# greenhouseSchematic.net
KiCad netlist of a schematic drawn in Altium Designer
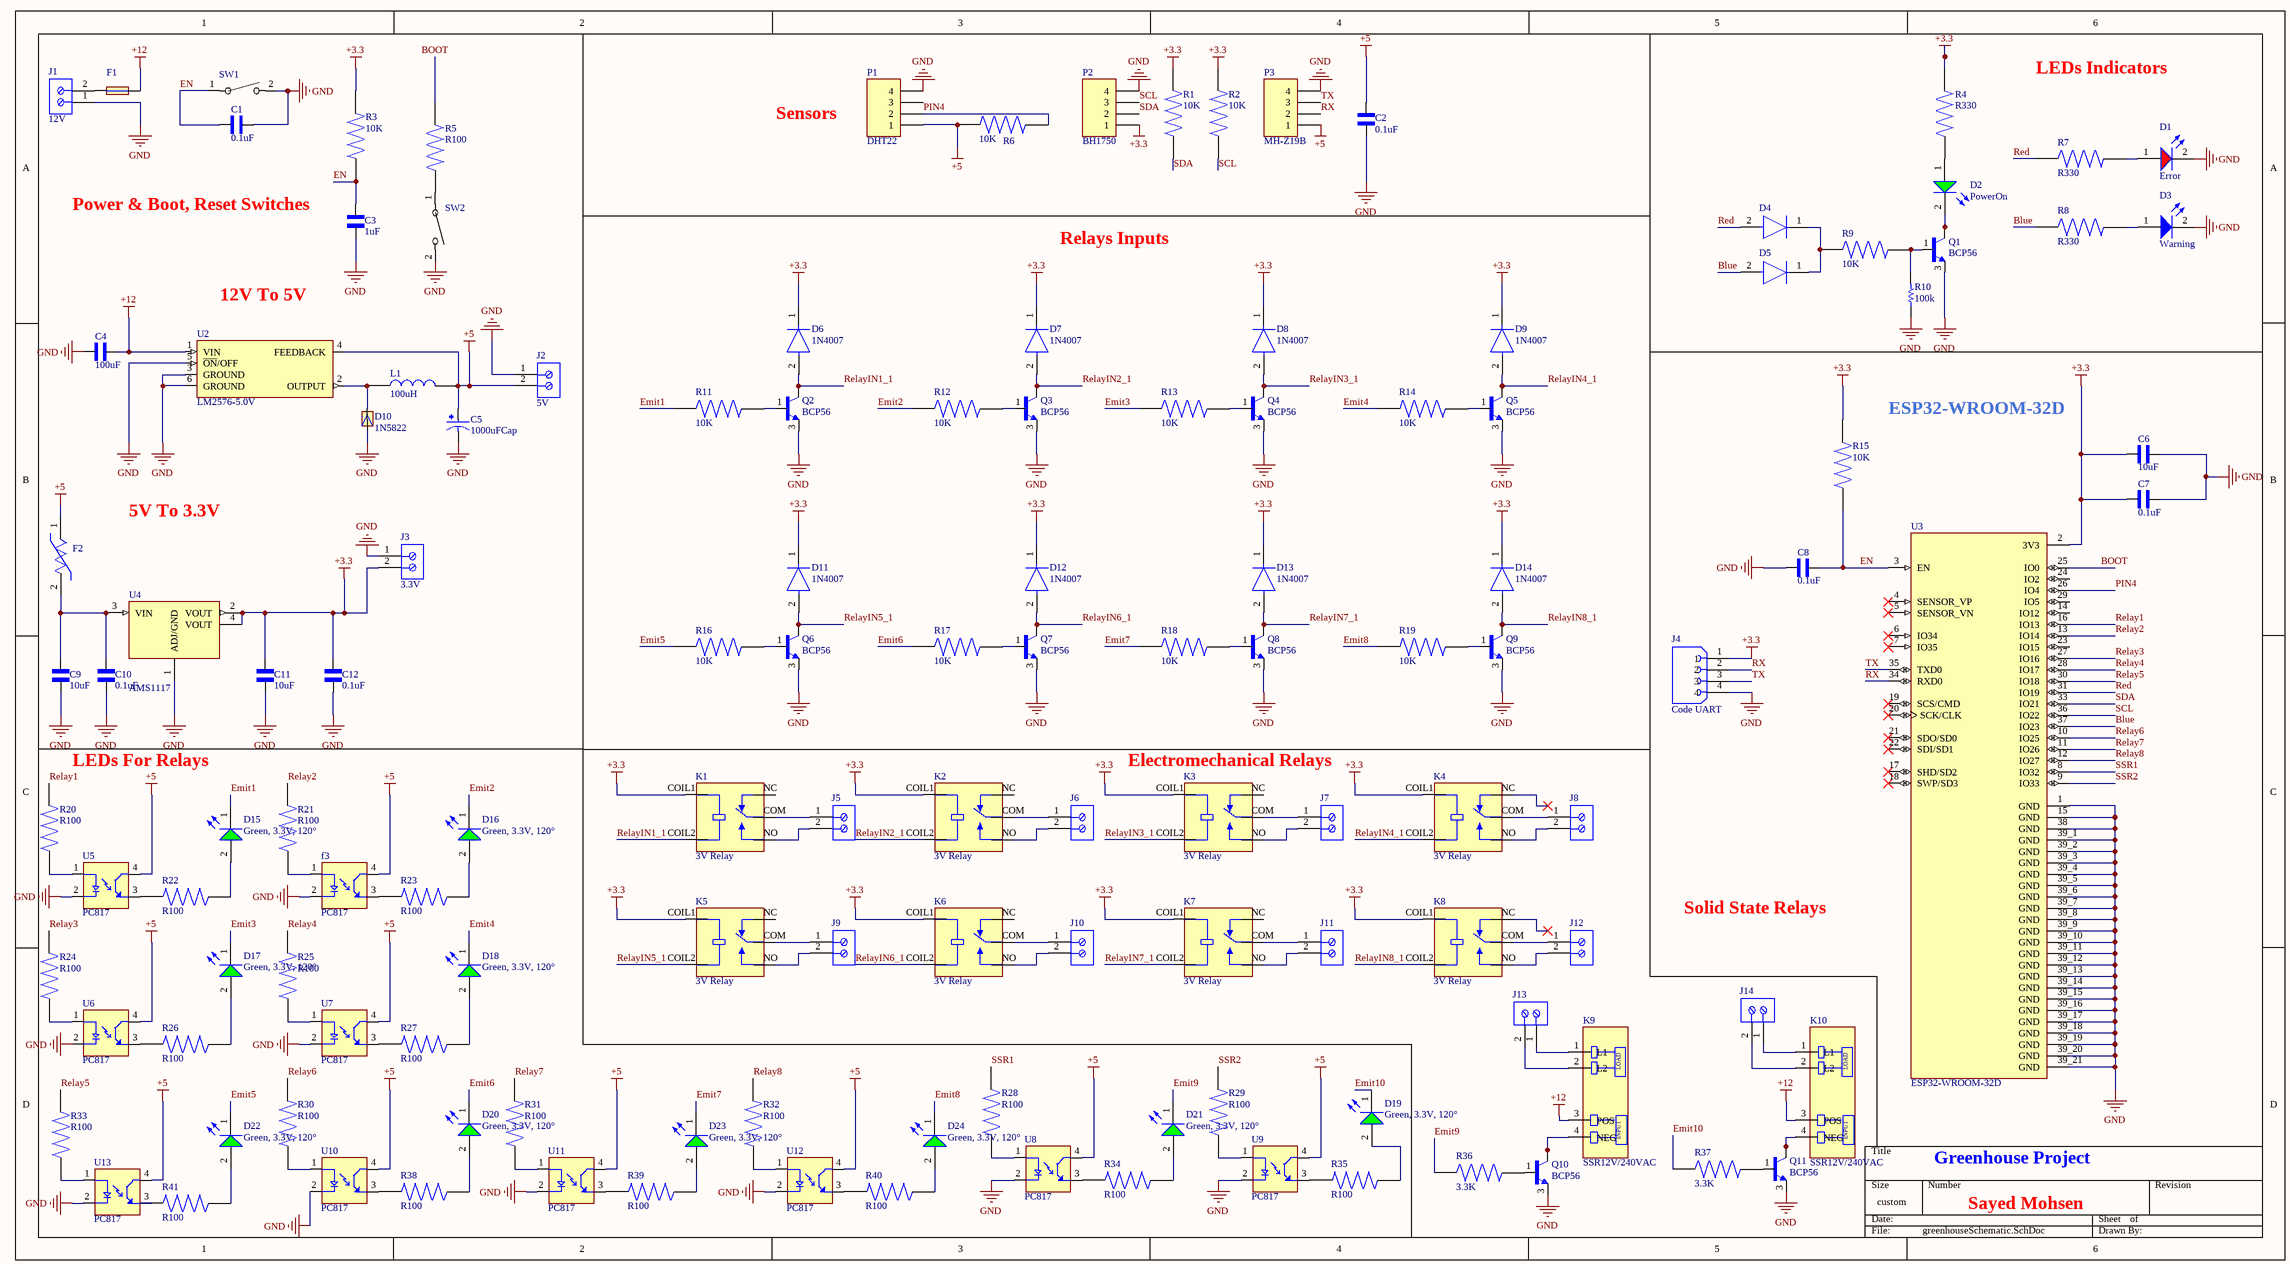
[diagram p0: greenhouseSchematic.SchDoc]

(export (version "E")
  (design (tool "Eeschema 10.0.6"))
  (components
    (comp (ref "C1")
      (value "0.1uF")
      (footprint "Capacitor0.1uF")
      (description "SMD Capacitor X7S(EIA) with Capacitance: 0.10uF Tol. 10%. Rated Voltage: 16Vdc")
      (fields (field (name "MF") "Murata") (field (name "MP") "GRM033C71C104KE14D"))
      (libsource (lib "greenhouse_SchLib") (part "Capacitor0.1uF"))
    )
    (comp (ref "C2")
      (value "0.1uF")
      (footprint "Capacitor0.1uF")
      (description "SMD Capacitor X7S(EIA) with Capacitance: 0.10uF Tol. 10%. Rated Voltage: 16Vdc")
      (fields (field (name "MF") "Murata") (field (name "MP") "GRM033C71C104KE14D"))
      (libsource (lib "") (part "Capacitor0.1uF_1"))
    )
    (comp (ref "C3")
      (value "1uF")
      (footprint "CAPACITOR1UF")
      (description "SMD capacitor X5R(EIA) with capacitance 1.0uF Tol.20%. Rated voltage 10Vdc 85C")
      (fields (field (name "MF") "Murata") (field (name "MP") "GRM033R61A105ME44J"))
      (libsource (lib "greenhouse_SchLib") (part "Capacitor1uF"))
    )
    (comp (ref "C4")
      (value "100uF")
      (footprint "Capacitor10uF")
      (description "SMD Capacitor X5R(EIA) with Capacitance: 10uF Tol. 10%. Rated Voltage: 10Vdc")
      (fields (field (name "MF") "Murata") (field (name "MP") "GRM21BR61A106KE19K"))
      (libsource (lib "greenhouse_SchLib") (part "Capacitor10uF"))
    )
    (comp (ref "C5")
      (value "1000uFCap")
      (footprint "1000uFCap")
      (description "CAP ALUM 1000UF 20% 10V SMD")
      (fields (field (name "MP") "EEE-FN1A102P") (field (name "MF") "Panasonic Electronic Components"))
      (libsource (lib "greenhouse_SchLib") (part "1000uFCap"))
    )
    (comp (ref "C6")
      (value "10uF")
      (footprint "Capacitor10uF")
      (description "SMD Capacitor X5R(EIA) with Capacitance: 10uF Tol. 10%. Rated Voltage: 10Vdc")
      (fields (field (name "MF") "Murata") (field (name "MP") "GRM21BR61A106KE19K"))
      (libsource (lib "") (part "Capacitor10uF_1"))
    )
    (comp (ref "C7")
      (value "0.1uF")
      (footprint "Capacitor0.1uF")
      (description "SMD Capacitor X7S(EIA) with Capacitance: 0.10uF Tol. 10%. Rated Voltage: 16Vdc")
      (fields (field (name "MF") "Murata") (field (name "MP") "GRM033C71C104KE14D"))
      (libsource (lib "greenhouse_SchLib") (part "Capacitor0.1uF"))
    )
    (comp (ref "C8")
      (value "0.1uF")
      (footprint "Capacitor0.1uF")
      (description "SMD Capacitor X7S(EIA) with Capacitance: 0.10uF Tol. 10%. Rated Voltage: 16Vdc")
      (fields (field (name "MF") "Murata") (field (name "MP") "GRM033C71C104KE14D"))
      (libsource (lib "greenhouse_SchLib") (part "Capacitor0.1uF"))
    )
    (comp (ref "C9")
      (value "10uF")
      (footprint "Capacitor10uF")
      (description "SMD Capacitor X5R(EIA) with Capacitance: 10uF Tol. 10%. Rated Voltage: 10Vdc")
      (fields (field (name "MF") "Murata") (field (name "MP") "GRM21BR61A106KE19K"))
      (libsource (lib "") (part "Capacitor10uF_2"))
    )
    (comp (ref "C10")
      (value "0.1uF")
      (footprint "Capacitor0.1uF")
      (description "SMD Capacitor X7S(EIA) with Capacitance: 0.10uF Tol. 10%. Rated Voltage: 16Vdc")
      (fields (field (name "MF") "Murata") (field (name "MP") "GRM033C71C104KE14D"))
      (libsource (lib "") (part "Capacitor0.1uF_1"))
    )
    (comp (ref "C11")
      (value "10uF")
      (footprint "Capacitor10uF")
      (description "SMD Capacitor X5R(EIA) with Capacitance: 10uF Tol. 10%. Rated Voltage: 10Vdc")
      (fields (field (name "MF") "Murata") (field (name "MP") "GRM21BR61A106KE19K"))
      (libsource (lib "") (part "Capacitor10uF_2"))
    )
    (comp (ref "C12")
      (value "0.1uF")
      (footprint "Capacitor0.1uF")
      (description "SMD Capacitor X7S(EIA) with Capacitance: 0.10uF Tol. 10%. Rated Voltage: 16Vdc")
      (fields (field (name "MF") "Murata") (field (name "MP") "GRM033C71C104KE14D"))
      (libsource (lib "") (part "Capacitor0.1uF_1"))
    )
    (comp (ref "D1")
      (value "Error")
      (footprint "redLed")
      (libsource (lib "greenhouse_SchLib") (part "redLed"))
    )
    (comp (ref "D2")
      (value "PowerOn")
      (footprint "greenLed")
      (libsource (lib "greenhouse_SchLib") (part "greenLed"))
    )
    (comp (ref "D3")
      (value "Warning")
      (footprint "blueLed")
      (libsource (lib "greenhouse_SchLib") (part "blueLed"))
    )
    (comp (ref "D4")
      (value "1N4007")
      (footprint "1N4007")
      (description "Rectifier diode 1000 V 1 A DO-41, ,")
      (fields
        (field (name "MANUFACTURER") "Diotec")
        (field (name "OCTOPART") "https://octopart.com/1n4007-diotec-4040411")
      )
      (libsource (lib "greenhouse_SchLib") (part "1N4007"))
    )
    (comp (ref "D5")
      (value "1N4007")
      (footprint "1N4007")
      (description "Rectifier diode 1000 V 1 A DO-41, ,")
      (fields
        (field (name "MANUFACTURER") "Diotec")
        (field (name "OCTOPART") "https://octopart.com/1n4007-diotec-4040411")
      )
      (libsource (lib "greenhouse_SchLib") (part "1N4007"))
    )
    (comp (ref "D6")
      (value "1N4007")
      (footprint "1N4007")
      (description "Rectifier diode 1000 V 1 A DO-41, ,")
      (fields
        (field (name "MANUFACTURER") "Diotec")
        (field (name "OCTOPART") "https://octopart.com/1n4007-diotec-4040411")
      )
      (libsource (lib "greenhouse_SchLib") (part "1N4007"))
    )
    (comp (ref "D7")
      (value "1N4007")
      (footprint "1N4007")
      (description "Rectifier diode 1000 V 1 A DO-41, ,")
      (fields
        (field (name "MANUFACTURER") "Diotec")
        (field (name "OCTOPART") "https://octopart.com/1n4007-diotec-4040411")
      )
      (libsource (lib "greenhouse_SchLib") (part "1N4007"))
    )
    (comp (ref "D8")
      (value "1N4007")
      (footprint "1N4007")
      (description "Rectifier diode 1000 V 1 A DO-41, ,")
      (fields
        (field (name "MANUFACTURER") "Diotec")
        (field (name "OCTOPART") "https://octopart.com/1n4007-diotec-4040411")
      )
      (libsource (lib "greenhouse_SchLib") (part "1N4007"))
    )
    (comp (ref "D9")
      (value "1N4007")
      (footprint "1N4007")
      (description "Rectifier diode 1000 V 1 A DO-41, ,")
      (fields
        (field (name "MANUFACTURER") "Diotec")
        (field (name "OCTOPART") "https://octopart.com/1n4007-diotec-4040411")
      )
      (libsource (lib "greenhouse_SchLib") (part "1N4007"))
    )
    (comp (ref "D10")
      (value "1N5822")
      (footprint "1N5822Diode")
      (description "Schottky, DO-201, 40V, 3A, 150Â°C")
      (fields (field (name "MF") "Diotec Semiconductor"))
      (libsource (lib "greenhouse_SchLib") (part "1N5822 Diode"))
    )
    (comp (ref "D11")
      (value "1N4007")
      (footprint "1N4007")
      (description "Rectifier diode 1000 V 1 A DO-41, ,")
      (fields
        (field (name "MANUFACTURER") "Diotec")
        (field (name "OCTOPART") "https://octopart.com/1n4007-diotec-4040411")
      )
      (libsource (lib "greenhouse_SchLib") (part "1N4007"))
    )
    (comp (ref "D12")
      (value "1N4007")
      (footprint "1N4007")
      (description "Rectifier diode 1000 V 1 A DO-41, ,")
      (fields
        (field (name "MANUFACTURER") "Diotec")
        (field (name "OCTOPART") "https://octopart.com/1n4007-diotec-4040411")
      )
      (libsource (lib "greenhouse_SchLib") (part "1N4007"))
    )
    (comp (ref "D13")
      (value "1N4007")
      (footprint "1N4007")
      (description "Rectifier diode 1000 V 1 A DO-41, ,")
      (fields
        (field (name "MANUFACTURER") "Diotec")
        (field (name "OCTOPART") "https://octopart.com/1n4007-diotec-4040411")
      )
      (libsource (lib "greenhouse_SchLib") (part "1N4007"))
    )
    (comp (ref "D14")
      (value "1N4007")
      (footprint "1N4007")
      (description "Rectifier diode 1000 V 1 A DO-41, ,")
      (fields
        (field (name "MANUFACTURER") "Diotec")
        (field (name "OCTOPART") "https://octopart.com/1n4007-diotec-4040411")
      )
      (libsource (lib "greenhouse_SchLib") (part "1N4007"))
    )
    (comp (ref "D15")
      (value "Green, 3.3V, 120°")
      (footprint "newgreenled")
      (description "WL-SMCC Mono-color Chip LED Compact, SMT, size 0402, Green, 3.3V, 120°")
      (fields
        (field (name "MANUFACTURER PART NUMBER") "150040GS73220")
        (field (name "MANUFACTURER") "Wurth Elektronik")
      )
      (libsource (lib "greenhouse_SchLib") (part "GreenLed_1"))
    )
    (comp (ref "D16")
      (value "Green, 3.3V, 120°")
      (footprint "newgreenled")
      (description "WL-SMCC Mono-color Chip LED Compact, SMT, size 0402, Green, 3.3V, 120°")
      (fields
        (field (name "MANUFACTURER PART NUMBER") "150040GS73220")
        (field (name "MANUFACTURER") "Wurth Elektronik")
      )
      (libsource (lib "greenhouse_SchLib") (part "GreenLed_1"))
    )
    (comp (ref "D17")
      (value "Green, 3.3V, 120°")
      (footprint "newgreenled")
      (description "WL-SMCC Mono-color Chip LED Compact, SMT, size 0402, Green, 3.3V, 120°")
      (fields
        (field (name "MANUFACTURER PART NUMBER") "150040GS73220")
        (field (name "MANUFACTURER") "Wurth Elektronik")
      )
      (libsource (lib "greenhouse_SchLib") (part "GreenLed_1"))
    )
    (comp (ref "D18")
      (value "Green, 3.3V, 120°")
      (footprint "newgreenled")
      (description "WL-SMCC Mono-color Chip LED Compact, SMT, size 0402, Green, 3.3V, 120°")
      (fields
        (field (name "MANUFACTURER PART NUMBER") "150040GS73220")
        (field (name "MANUFACTURER") "Wurth Elektronik")
      )
      (libsource (lib "greenhouse_SchLib") (part "GreenLed_1"))
    )
    (comp (ref "D19")
      (value "Green, 3.3V, 120°")
      (footprint "newgreenled")
      (description "WL-SMCC Mono-color Chip LED Compact, SMT, size 0402, Green, 3.3V, 120°")
      (fields
        (field (name "MANUFACTURER PART NUMBER") "150040GS73220")
        (field (name "MANUFACTURER") "Wurth Elektronik")
      )
      (libsource (lib "greenhouse_SchLib") (part "GreenLed_1"))
    )
    (comp (ref "D20")
      (value "Green, 3.3V, 120°")
      (footprint "newgreenled")
      (description "WL-SMCC Mono-color Chip LED Compact, SMT, size 0402, Green, 3.3V, 120°")
      (fields
        (field (name "MANUFACTURER PART NUMBER") "150040GS73220")
        (field (name "MANUFACTURER") "Wurth Elektronik")
      )
      (libsource (lib "greenhouse_SchLib") (part "GreenLed_1"))
    )
    (comp (ref "D21")
      (value "Green, 3.3V, 120°")
      (footprint "newgreenled")
      (description "WL-SMCC Mono-color Chip LED Compact, SMT, size 0402, Green, 3.3V, 120°")
      (fields
        (field (name "MANUFACTURER PART NUMBER") "150040GS73220")
        (field (name "MANUFACTURER") "Wurth Elektronik")
      )
      (libsource (lib "greenhouse_SchLib") (part "GreenLed_1"))
    )
    (comp (ref "D22")
      (value "Green, 3.3V, 120°")
      (footprint "newgreenled")
      (description "WL-SMCC Mono-color Chip LED Compact, SMT, size 0402, Green, 3.3V, 120°")
      (fields
        (field (name "MANUFACTURER PART NUMBER") "150040GS73220")
        (field (name "MANUFACTURER") "Wurth Elektronik")
      )
      (libsource (lib "greenhouse_SchLib") (part "GreenLed_1"))
    )
    (comp (ref "D23")
      (value "Green, 3.3V, 120°")
      (footprint "newgreenled")
      (description "WL-SMCC Mono-color Chip LED Compact, SMT, size 0402, Green, 3.3V, 120°")
      (fields
        (field (name "MANUFACTURER PART NUMBER") "150040GS73220")
        (field (name "MANUFACTURER") "Wurth Elektronik")
      )
      (libsource (lib "greenhouse_SchLib") (part "GreenLed_1"))
    )
    (comp (ref "D24")
      (value "Green, 3.3V, 120°")
      (footprint "newgreenled")
      (description "WL-SMCC Mono-color Chip LED Compact, SMT, size 0402, Green, 3.3V, 120°")
      (fields
        (field (name "MANUFACTURER PART NUMBER") "150040GS73220")
        (field (name "MANUFACTURER") "Wurth Elektronik")
      )
      (libsource (lib "greenhouse_SchLib") (part "GreenLed_1"))
    )
    (comp (ref "F1")
      (value "1812L200/12DR")
      (footprint "FUSE_1812L200/12DR")
      (description "Polymeric PTC Resettable Fuse 12V 2A Ih Surface Mount 1812 (4532 Metric), Concave")
      (fields (field (name "MF") "Littelfuse Inc."))
      (libsource (lib "greenhouse_SchLib") (part "1812L200/12DR"))
    )
    (comp (ref "F2")
      (value "0ZCK0075FF2E")
      (footprint "ptc6v")
      (description "PTC RESET FUSE 6V 750MA 0805")
      (libsource (lib "greenhouse_SchLib") (part "ptc6v"))
    )
    (comp (ref "f3")
      (value "PC817")
      (footprint "PC817")
      (description "Optocoupler DC-IN 1-CH Transistor DC-OUT 4-Pin DIP SMD T/R")
      (fields (field (name "MF") "Sharp Microelectronics") (field (name "MP") "PC817X2NIP1B"))
      (libsource (lib "greenhouse_SchLib") (part "PC817"))
    )
    (comp (ref "J1") (value "12V") (footprint "screw") (libsource (lib "") (part "screw_1")))
    (comp (ref "J2") (value "5V") (footprint "screw") (libsource (lib "") (part "screw_1")))
    (comp (ref "J3") (value "3.3V") (footprint "screw") (libsource (lib "") (part "screw_1")))
    (comp (ref "J4")
      (value "Code UART")
      (footprint "Fpinheader")
      (description "4 Position Header Connector 0.100 (2.54mm) Through Hole Tin")
      (fields (field (name "MF") "Sullins Connector") (field (name "MP") "PPTC041LFBN-RC"))
      (libsource (lib "greenhouse_SchLib") (part "FPinheader"))
    )
    (comp (ref "J5") (value "~") (footprint "screw") (libsource (lib "") (part "screw_1")))
    (comp (ref "J6") (value "~") (footprint "screw") (libsource (lib "") (part "screw_1")))
    (comp (ref "J7") (value "~") (footprint "screw") (libsource (lib "") (part "screw_1")))
    (comp (ref "J8") (value "~") (footprint "screw") (libsource (lib "") (part "screw_1")))
    (comp (ref "J9") (value "~") (footprint "screw") (libsource (lib "") (part "screw_1")))
    (comp (ref "J10") (value "~") (footprint "screw") (libsource (lib "") (part "screw_1")))
    (comp (ref "J11") (value "~") (footprint "screw") (libsource (lib "") (part "screw_1")))
    (comp (ref "J12") (value "~") (footprint "screw") (libsource (lib "") (part "screw_1")))
    (comp (ref "J13") (value "~") (footprint "screw") (libsource (lib "greenhouse_SchLib") (part "screw")))
    (comp (ref "J14") (value "~") (footprint "screw") (libsource (lib "greenhouse_SchLib") (part "screw")))
    (comp (ref "K1")
      (value "3V Relay")
      (footprint "3V Relay")
      (description "Relays General Purpose Non Latching 3VDC SPDT 10A (250VAC) Max 5PIN")
      (fields (field (name "MF") "Songle Relay") (field (name "MP") "SRD-03VDC-SL-C"))
      (libsource (lib "greenhouse_SchLib") (part "3V Relay"))
    )
    (comp (ref "K2")
      (value "3V Relay")
      (footprint "3V Relay")
      (description "Relays General Purpose Non Latching 3VDC SPDT 10A (250VAC) Max 5PIN")
      (fields (field (name "MF") "Songle Relay") (field (name "MP") "SRD-03VDC-SL-C"))
      (libsource (lib "greenhouse_SchLib") (part "3V Relay"))
    )
    (comp (ref "K3")
      (value "3V Relay")
      (footprint "3V Relay")
      (description "Relays General Purpose Non Latching 3VDC SPDT 10A (250VAC) Max 5PIN")
      (fields (field (name "MF") "Songle Relay") (field (name "MP") "SRD-03VDC-SL-C"))
      (libsource (lib "greenhouse_SchLib") (part "3V Relay"))
    )
    (comp (ref "K4")
      (value "3V Relay")
      (footprint "3V Relay")
      (description "Relays General Purpose Non Latching 3VDC SPDT 10A (250VAC) Max 5PIN")
      (fields (field (name "MF") "Songle Relay") (field (name "MP") "SRD-03VDC-SL-C"))
      (libsource (lib "greenhouse_SchLib") (part "3V Relay"))
    )
    (comp (ref "K5")
      (value "3V Relay")
      (footprint "3V Relay")
      (description "Relays General Purpose Non Latching 3VDC SPDT 10A (250VAC) Max 5PIN")
      (fields (field (name "MF") "Songle Relay") (field (name "MP") "SRD-03VDC-SL-C"))
      (libsource (lib "greenhouse_SchLib") (part "3V Relay"))
    )
    (comp (ref "K6")
      (value "3V Relay")
      (footprint "3V Relay")
      (description "Relays General Purpose Non Latching 3VDC SPDT 10A (250VAC) Max 5PIN")
      (fields (field (name "MF") "Songle Relay") (field (name "MP") "SRD-03VDC-SL-C"))
      (libsource (lib "greenhouse_SchLib") (part "3V Relay"))
    )
    (comp (ref "K7")
      (value "3V Relay")
      (footprint "3V Relay")
      (description "Relays General Purpose Non Latching 3VDC SPDT 10A (250VAC) Max 5PIN")
      (fields (field (name "MF") "Songle Relay") (field (name "MP") "SRD-03VDC-SL-C"))
      (libsource (lib "greenhouse_SchLib") (part "3V Relay"))
    )
    (comp (ref "K8")
      (value "3V Relay")
      (footprint "3V Relay")
      (description "Relays General Purpose Non Latching 3VDC SPDT 10A (250VAC) Max 5PIN")
      (fields (field (name "MF") "Songle Relay") (field (name "MP") "SRD-03VDC-SL-C"))
      (libsource (lib "greenhouse_SchLib") (part "3V Relay"))
    )
    (comp (ref "K9")
      (value "SSR12V/240VAC")
      (footprint "SSR12V/240VAC")
      (description "Solid State SPST-NO (1 Form A) 4-SIP")
      (fields (field (name "MF") "Omron Automation") (field (name "MP") "G3MB-202P DC12"))
      (libsource (lib "greenhouse_SchLib") (part "SSR12V/240VAC"))
    )
    (comp (ref "K10")
      (value "SSR12V/240VAC")
      (footprint "SSR12V/240VAC")
      (description "Solid State SPST-NO (1 Form A) 4-SIP")
      (fields (field (name "MF") "Omron Automation") (field (name "MP") "G3MB-202P DC12"))
      (libsource (lib "greenhouse_SchLib") (part "SSR12V/240VAC"))
    )
    (comp (ref "L1")
      (value "100uH")
      (footprint "100uH Inductor")
      (description "Inductor with Inductance 100uH Tol.+/-20% Package 1212 (3030)")
      (fields (field (name "MF") "Murata") (field (name "MP") "LQH3NPH101MMEL"))
      (libsource (lib "greenhouse_SchLib") (part "100uH Inductor"))
    )
    (comp (ref "P1")
      (value "DHT22")
      (footprint "HDR1X4")
      (description "Header, 4-Pin")
      (fields (field (name "PUBLISHER") "Altium Limited"))
      (libsource (lib "Miscellaneous Connectors") (part "Header 4"))
    )
    (comp (ref "P2")
      (value "BH1750")
      (footprint "HDR1X4")
      (description "Header, 4-Pin")
      (fields (field (name "PUBLISHER") "Altium Limited"))
      (libsource (lib "Miscellaneous Connectors") (part "Header 4"))
    )
    (comp (ref "P3")
      (value "MH-Z19B")
      (footprint "HDR1X4")
      (description "Header, 4-Pin")
      (fields (field (name "PUBLISHER") "Altium Limited"))
      (libsource (lib "Miscellaneous Connectors") (part "Header 4"))
    )
    (comp (ref "Q1")
      (value "BCP56")
      (footprint "BCP56")
      (description "Bipolar (BJT) Transistor NPN 80 V 1 A 130MHz 1.5 W Surface Mount SOT-223 (TO-261)")
      (fields (field (name "MF") "ON Semiconductor"))
      (libsource (lib "greenhouse_SchLib") (part "BCP56"))
    )
    (comp (ref "Q2")
      (value "BCP56")
      (footprint "BCP56")
      (description "Bipolar (BJT) Transistor NPN 80 V 1 A 130MHz 1.5 W Surface Mount SOT-223 (TO-261)")
      (fields (field (name "MF") "ON Semiconductor"))
      (libsource (lib "greenhouse_SchLib") (part "BCP56"))
    )
    (comp (ref "Q3")
      (value "BCP56")
      (footprint "BCP56")
      (description "Bipolar (BJT) Transistor NPN 80 V 1 A 130MHz 1.5 W Surface Mount SOT-223 (TO-261)")
      (fields (field (name "MF") "ON Semiconductor"))
      (libsource (lib "greenhouse_SchLib") (part "BCP56"))
    )
    (comp (ref "Q4")
      (value "BCP56")
      (footprint "BCP56")
      (description "Bipolar (BJT) Transistor NPN 80 V 1 A 130MHz 1.5 W Surface Mount SOT-223 (TO-261)")
      (fields (field (name "MF") "ON Semiconductor"))
      (libsource (lib "greenhouse_SchLib") (part "BCP56"))
    )
    (comp (ref "Q5")
      (value "BCP56")
      (footprint "BCP56")
      (description "Bipolar (BJT) Transistor NPN 80 V 1 A 130MHz 1.5 W Surface Mount SOT-223 (TO-261)")
      (fields (field (name "MF") "ON Semiconductor"))
      (libsource (lib "greenhouse_SchLib") (part "BCP56"))
    )
    (comp (ref "Q6")
      (value "BCP56")
      (footprint "BCP56")
      (description "Bipolar (BJT) Transistor NPN 80 V 1 A 130MHz 1.5 W Surface Mount SOT-223 (TO-261)")
      (fields (field (name "MF") "ON Semiconductor"))
      (libsource (lib "greenhouse_SchLib") (part "BCP56"))
    )
    (comp (ref "Q7")
      (value "BCP56")
      (footprint "BCP56")
      (description "Bipolar (BJT) Transistor NPN 80 V 1 A 130MHz 1.5 W Surface Mount SOT-223 (TO-261)")
      (fields (field (name "MF") "ON Semiconductor"))
      (libsource (lib "greenhouse_SchLib") (part "BCP56"))
    )
    (comp (ref "Q8")
      (value "BCP56")
      (footprint "BCP56")
      (description "Bipolar (BJT) Transistor NPN 80 V 1 A 130MHz 1.5 W Surface Mount SOT-223 (TO-261)")
      (fields (field (name "MF") "ON Semiconductor"))
      (libsource (lib "greenhouse_SchLib") (part "BCP56"))
    )
    (comp (ref "Q9")
      (value "BCP56")
      (footprint "BCP56")
      (description "Bipolar (BJT) Transistor NPN 80 V 1 A 130MHz 1.5 W Surface Mount SOT-223 (TO-261)")
      (fields (field (name "MF") "ON Semiconductor"))
      (libsource (lib "greenhouse_SchLib") (part "BCP56"))
    )
    (comp (ref "Q10")
      (value "BCP56")
      (footprint "BCP56")
      (description "Bipolar (BJT) Transistor NPN 80 V 1 A 130MHz 1.5 W Surface Mount SOT-223 (TO-261)")
      (fields (field (name "MF") "ON Semiconductor"))
      (libsource (lib "greenhouse_SchLib") (part "BCP56"))
    )
    (comp (ref "Q11")
      (value "BCP56")
      (footprint "BCP56")
      (description "Bipolar (BJT) Transistor NPN 80 V 1 A 130MHz 1.5 W Surface Mount SOT-223 (TO-261)")
      (fields (field (name "MF") "ON Semiconductor"))
      (libsource (lib "greenhouse_SchLib") (part "BCP56"))
    )
    (comp (ref "R1")
      (value "10K")
      (footprint "Resistor10K")
      (description "Res Thick Film 0201 10K Ohm 1% 1/20W 200ppm/C Molded SMD SMD Pressed Carrier T/R")
      (fields (field (name "MF") "Panasonic") (field (name "MP") "ERJ-U01F1002C"))
      (libsource (lib "greenhouse_SchLib") (part "Resistor10K"))
    )
    (comp (ref "R2")
      (value "10K")
      (footprint "Resistor10K")
      (description "Res Thick Film 0201 10K Ohm 1% 1/20W 200ppm/C Molded SMD SMD Pressed Carrier T/R")
      (fields (field (name "MF") "Panasonic") (field (name "MP") "ERJ-U01F1002C"))
      (libsource (lib "greenhouse_SchLib") (part "Resistor10K"))
    )
    (comp (ref "R3")
      (value "10K")
      (footprint "Resistor10K")
      (description "Res Thick Film 0201 10K Ohm 1% 1/20W 200ppm/C Molded SMD SMD Pressed Carrier T/R")
      (fields (field (name "MF") "Panasonic") (field (name "MP") "ERJ-U01F1002C"))
      (libsource (lib "greenhouse_SchLib") (part "Resistor10K"))
    )
    (comp (ref "R4")
      (value "R330")
      (footprint "R100")
      (description "Res Thin Film 0402 100 Ohm 0.5% 0.063W(1/16W) Â±25ppm/C Molded SMD Paper T/R")
      (fields (field (name "MF") "Stackpole Electronics Inc") (field (name "MP") "RNCF0402DTE100R"))
      (libsource (lib "greenhouse_SchLib") (part "R100"))
    )
    (comp (ref "R5")
      (value "R100")
      (footprint "R100")
      (description "Res Thin Film 0402 100 Ohm 0.5% 0.063W(1/16W) Â±25ppm/C Molded SMD Paper T/R")
      (fields (field (name "MF") "Stackpole Electronics Inc") (field (name "MP") "RNCF0402DTE100R"))
      (libsource (lib "greenhouse_SchLib") (part "R100"))
    )
    (comp (ref "R6")
      (value "10K")
      (footprint "Resistor10K")
      (description "Res Thick Film 0201 10K Ohm 1% 1/20W 200ppm/C Molded SMD SMD Pressed Carrier T/R")
      (fields (field (name "MF") "Panasonic") (field (name "MP") "ERJ-U01F1002C"))
      (libsource (lib "greenhouse_SchLib") (part "Resistor10K"))
    )
    (comp (ref "R7")
      (value "R330")
      (footprint "R100")
      (description "Res Thin Film 0402 100 Ohm 0.5% 0.063W(1/16W) Â±25ppm/C Molded SMD Paper T/R")
      (fields (field (name "MF") "Stackpole Electronics Inc") (field (name "MP") "RNCF0402DTE100R"))
      (libsource (lib "greenhouse_SchLib") (part "R100"))
    )
    (comp (ref "R8")
      (value "R330")
      (footprint "R100")
      (description "Res Thin Film 0402 100 Ohm 0.5% 0.063W(1/16W) Â±25ppm/C Molded SMD Paper T/R")
      (fields (field (name "MF") "Stackpole Electronics Inc") (field (name "MP") "RNCF0402DTE100R"))
      (libsource (lib "greenhouse_SchLib") (part "R100"))
    )
    (comp (ref "R9")
      (value "10K")
      (footprint "Resistor10K")
      (description "Res Thick Film 0201 10K Ohm 1% 1/20W 200ppm/C Molded SMD SMD Pressed Carrier T/R")
      (fields (field (name "MF") "Panasonic") (field (name "MP") "ERJ-U01F1002C"))
      (libsource (lib "greenhouse_SchLib") (part "Resistor10K"))
    )
    (comp (ref "R10")
      (value "100k")
      (footprint "RESC1608X55X30ML15T15")
      (fields (field (name "PART NUMBER") "ERJ-3EKF1003V") (field (name "MANUFACTURER") "Panasonic"))
      (libsource (lib "Altium Content Vault") (part "RES"))
    )
    (comp (ref "R11")
      (value "10K")
      (footprint "Resistor10K")
      (description "Res Thick Film 0201 10K Ohm 1% 1/20W 200ppm/C Molded SMD SMD Pressed Carrier T/R")
      (fields (field (name "MF") "Panasonic") (field (name "MP") "ERJ-U01F1002C"))
      (libsource (lib "greenhouse_SchLib") (part "Resistor10K"))
    )
    (comp (ref "R12")
      (value "10K")
      (footprint "Resistor10K")
      (description "Res Thick Film 0201 10K Ohm 1% 1/20W 200ppm/C Molded SMD SMD Pressed Carrier T/R")
      (fields (field (name "MF") "Panasonic") (field (name "MP") "ERJ-U01F1002C"))
      (libsource (lib "greenhouse_SchLib") (part "Resistor10K"))
    )
    (comp (ref "R13")
      (value "10K")
      (footprint "Resistor10K")
      (description "Res Thick Film 0201 10K Ohm 1% 1/20W 200ppm/C Molded SMD SMD Pressed Carrier T/R")
      (fields (field (name "MF") "Panasonic") (field (name "MP") "ERJ-U01F1002C"))
      (libsource (lib "greenhouse_SchLib") (part "Resistor10K"))
    )
    (comp (ref "R14")
      (value "10K")
      (footprint "Resistor10K")
      (description "Res Thick Film 0201 10K Ohm 1% 1/20W 200ppm/C Molded SMD SMD Pressed Carrier T/R")
      (fields (field (name "MF") "Panasonic") (field (name "MP") "ERJ-U01F1002C"))
      (libsource (lib "greenhouse_SchLib") (part "Resistor10K"))
    )
    (comp (ref "R15")
      (value "10K")
      (footprint "Resistor10K")
      (description "Res Thick Film 0201 10K Ohm 1% 1/20W 200ppm/C Molded SMD SMD Pressed Carrier T/R")
      (fields (field (name "MF") "Panasonic") (field (name "MP") "ERJ-U01F1002C"))
      (libsource (lib "greenhouse_SchLib") (part "Resistor10K"))
    )
    (comp (ref "R16")
      (value "10K")
      (footprint "Resistor10K")
      (description "Res Thick Film 0201 10K Ohm 1% 1/20W 200ppm/C Molded SMD SMD Pressed Carrier T/R")
      (fields (field (name "MF") "Panasonic") (field (name "MP") "ERJ-U01F1002C"))
      (libsource (lib "greenhouse_SchLib") (part "Resistor10K"))
    )
    (comp (ref "R17")
      (value "10K")
      (footprint "Resistor10K")
      (description "Res Thick Film 0201 10K Ohm 1% 1/20W 200ppm/C Molded SMD SMD Pressed Carrier T/R")
      (fields (field (name "MF") "Panasonic") (field (name "MP") "ERJ-U01F1002C"))
      (libsource (lib "greenhouse_SchLib") (part "Resistor10K"))
    )
    (comp (ref "R18")
      (value "10K")
      (footprint "Resistor10K")
      (description "Res Thick Film 0201 10K Ohm 1% 1/20W 200ppm/C Molded SMD SMD Pressed Carrier T/R")
      (fields (field (name "MF") "Panasonic") (field (name "MP") "ERJ-U01F1002C"))
      (libsource (lib "greenhouse_SchLib") (part "Resistor10K"))
    )
    (comp (ref "R19")
      (value "10K")
      (footprint "Resistor10K")
      (description "Res Thick Film 0201 10K Ohm 1% 1/20W 200ppm/C Molded SMD SMD Pressed Carrier T/R")
      (fields (field (name "MF") "Panasonic") (field (name "MP") "ERJ-U01F1002C"))
      (libsource (lib "greenhouse_SchLib") (part "Resistor10K"))
    )
    (comp (ref "R20")
      (value "R100")
      (footprint "R100")
      (description "Res Thin Film 0402 100 Ohm 0.5% 0.063W(1/16W) Â±25ppm/C Molded SMD Paper T/R")
      (fields (field (name "MF") "Stackpole Electronics Inc") (field (name "MP") "RNCF0402DTE100R"))
      (libsource (lib "greenhouse_SchLib") (part "R100"))
    )
    (comp (ref "R21")
      (value "R100")
      (footprint "R100")
      (description "Res Thin Film 0402 100 Ohm 0.5% 0.063W(1/16W) Â±25ppm/C Molded SMD Paper T/R")
      (fields (field (name "MF") "Stackpole Electronics Inc") (field (name "MP") "RNCF0402DTE100R"))
      (libsource (lib "greenhouse_SchLib") (part "R100"))
    )
    (comp (ref "R22")
      (value "R100")
      (footprint "R100")
      (description "Res Thin Film 0402 100 Ohm 0.5% 0.063W(1/16W) Â±25ppm/C Molded SMD Paper T/R")
      (fields (field (name "MF") "Stackpole Electronics Inc") (field (name "MP") "RNCF0402DTE100R"))
      (libsource (lib "greenhouse_SchLib") (part "R100"))
    )
    (comp (ref "R23")
      (value "R100")
      (footprint "R100")
      (description "Res Thin Film 0402 100 Ohm 0.5% 0.063W(1/16W) Â±25ppm/C Molded SMD Paper T/R")
      (fields (field (name "MF") "Stackpole Electronics Inc") (field (name "MP") "RNCF0402DTE100R"))
      (libsource (lib "greenhouse_SchLib") (part "R100"))
    )
    (comp (ref "R24")
      (value "R100")
      (footprint "R100")
      (description "Res Thin Film 0402 100 Ohm 0.5% 0.063W(1/16W) Â±25ppm/C Molded SMD Paper T/R")
      (fields (field (name "MF") "Stackpole Electronics Inc") (field (name "MP") "RNCF0402DTE100R"))
      (libsource (lib "greenhouse_SchLib") (part "R100"))
    )
    (comp (ref "R25")
      (value "R100")
      (footprint "R100")
      (description "Res Thin Film 0402 100 Ohm 0.5% 0.063W(1/16W) Â±25ppm/C Molded SMD Paper T/R")
      (fields (field (name "MF") "Stackpole Electronics Inc") (field (name "MP") "RNCF0402DTE100R"))
      (libsource (lib "greenhouse_SchLib") (part "R100"))
    )
    (comp (ref "R26")
      (value "R100")
      (footprint "R100")
      (description "Res Thin Film 0402 100 Ohm 0.5% 0.063W(1/16W) Â±25ppm/C Molded SMD Paper T/R")
      (fields (field (name "MF") "Stackpole Electronics Inc") (field (name "MP") "RNCF0402DTE100R"))
      (libsource (lib "greenhouse_SchLib") (part "R100"))
    )
    (comp (ref "R27")
      (value "R100")
      (footprint "R100")
      (description "Res Thin Film 0402 100 Ohm 0.5% 0.063W(1/16W) Â±25ppm/C Molded SMD Paper T/R")
      (fields (field (name "MF") "Stackpole Electronics Inc") (field (name "MP") "RNCF0402DTE100R"))
      (libsource (lib "greenhouse_SchLib") (part "R100"))
    )
    (comp (ref "R28")
      (value "R100")
      (footprint "R100")
      (description "Res Thin Film 0402 100 Ohm 0.5% 0.063W(1/16W) Â±25ppm/C Molded SMD Paper T/R")
      (fields (field (name "MF") "Stackpole Electronics Inc") (field (name "MP") "RNCF0402DTE100R"))
      (libsource (lib "greenhouse_SchLib") (part "R100"))
    )
    (comp (ref "R29")
      (value "R100")
      (footprint "R100")
      (description "Res Thin Film 0402 100 Ohm 0.5% 0.063W(1/16W) Â±25ppm/C Molded SMD Paper T/R")
      (fields (field (name "MF") "Stackpole Electronics Inc") (field (name "MP") "RNCF0402DTE100R"))
      (libsource (lib "greenhouse_SchLib") (part "R100"))
    )
    (comp (ref "R30")
      (value "R100")
      (footprint "R100")
      (description "Res Thin Film 0402 100 Ohm 0.5% 0.063W(1/16W) Â±25ppm/C Molded SMD Paper T/R")
      (fields (field (name "MF") "Stackpole Electronics Inc") (field (name "MP") "RNCF0402DTE100R"))
      (libsource (lib "greenhouse_SchLib") (part "R100"))
    )
    (comp (ref "R31")
      (value "R100")
      (footprint "R100")
      (description "Res Thin Film 0402 100 Ohm 0.5% 0.063W(1/16W) Â±25ppm/C Molded SMD Paper T/R")
      (fields (field (name "MF") "Stackpole Electronics Inc") (field (name "MP") "RNCF0402DTE100R"))
      (libsource (lib "greenhouse_SchLib") (part "R100"))
    )
    (comp (ref "R32")
      (value "R100")
      (footprint "R100")
      (description "Res Thin Film 0402 100 Ohm 0.5% 0.063W(1/16W) Â±25ppm/C Molded SMD Paper T/R")
      (fields (field (name "MF") "Stackpole Electronics Inc") (field (name "MP") "RNCF0402DTE100R"))
      (libsource (lib "greenhouse_SchLib") (part "R100"))
    )
    (comp (ref "R33")
      (value "R100")
      (footprint "R100")
      (description "Res Thin Film 0402 100 Ohm 0.5% 0.063W(1/16W) Â±25ppm/C Molded SMD Paper T/R")
      (fields (field (name "MF") "Stackpole Electronics Inc") (field (name "MP") "RNCF0402DTE100R"))
      (libsource (lib "greenhouse_SchLib") (part "R100"))
    )
    (comp (ref "R34")
      (value "R100")
      (footprint "R100")
      (description "Res Thin Film 0402 100 Ohm 0.5% 0.063W(1/16W) Â±25ppm/C Molded SMD Paper T/R")
      (fields (field (name "MF") "Stackpole Electronics Inc") (field (name "MP") "RNCF0402DTE100R"))
      (libsource (lib "greenhouse_SchLib") (part "R100"))
    )
    (comp (ref "R35")
      (value "R100")
      (footprint "R100")
      (description "Res Thin Film 0402 100 Ohm 0.5% 0.063W(1/16W) Â±25ppm/C Molded SMD Paper T/R")
      (fields (field (name "MF") "Stackpole Electronics Inc") (field (name "MP") "RNCF0402DTE100R"))
      (libsource (lib "greenhouse_SchLib") (part "R100"))
    )
    (comp (ref "R36")
      (value "3.3K")
      (footprint "Resistor10K")
      (description "Res Thick Film 0201 10K Ohm 1% 1/20W 200ppm/C Molded SMD SMD Pressed Carrier T/R")
      (fields (field (name "MF") "Panasonic") (field (name "MP") "ERJ-U01F1002C"))
      (libsource (lib "greenhouse_SchLib") (part "Resistor10K"))
    )
    (comp (ref "R37")
      (value "3.3K")
      (footprint "Resistor10K")
      (description "Res Thick Film 0201 10K Ohm 1% 1/20W 200ppm/C Molded SMD SMD Pressed Carrier T/R")
      (fields (field (name "MF") "Panasonic") (field (name "MP") "ERJ-U01F1002C"))
      (libsource (lib "greenhouse_SchLib") (part "Resistor10K"))
    )
    (comp (ref "R38")
      (value "R100")
      (footprint "R100")
      (description "Res Thin Film 0402 100 Ohm 0.5% 0.063W(1/16W) Â±25ppm/C Molded SMD Paper T/R")
      (fields (field (name "MF") "Stackpole Electronics Inc") (field (name "MP") "RNCF0402DTE100R"))
      (libsource (lib "greenhouse_SchLib") (part "R100"))
    )
    (comp (ref "R39")
      (value "R100")
      (footprint "R100")
      (description "Res Thin Film 0402 100 Ohm 0.5% 0.063W(1/16W) Â±25ppm/C Molded SMD Paper T/R")
      (fields (field (name "MF") "Stackpole Electronics Inc") (field (name "MP") "RNCF0402DTE100R"))
      (libsource (lib "greenhouse_SchLib") (part "R100"))
    )
    (comp (ref "R40")
      (value "R100")
      (footprint "R100")
      (description "Res Thin Film 0402 100 Ohm 0.5% 0.063W(1/16W) Â±25ppm/C Molded SMD Paper T/R")
      (fields (field (name "MF") "Stackpole Electronics Inc") (field (name "MP") "RNCF0402DTE100R"))
      (libsource (lib "greenhouse_SchLib") (part "R100"))
    )
    (comp (ref "R41")
      (value "R100")
      (footprint "R100")
      (description "Res Thin Film 0402 100 Ohm 0.5% 0.063W(1/16W) Â±25ppm/C Molded SMD Paper T/R")
      (fields (field (name "MF") "Stackpole Electronics Inc") (field (name "MP") "RNCF0402DTE100R"))
      (libsource (lib "greenhouse_SchLib") (part "R100"))
    )
    (comp (ref "SW1")
      (value "PTS636 SM25F SMTR LFS")
      (footprint "Switch12v")
      (description "Description")
      (fields (field (name "COPYRIGHT") "Copyright (C) 2025 Ultra Librarian. All rights reserved."))
      (libsource (lib "greenhouse_SchLib") (part "Switch12v"))
    )
    (comp (ref "SW2")
      (value "PTS636 SM25F SMTR LFS")
      (footprint "Switch12v")
      (description "Description")
      (fields (field (name "COPYRIGHT") "Copyright (C) 2025 Ultra Librarian. All rights reserved."))
      (libsource (lib "") (part "Switch12v_1"))
    )
    (comp (ref "U2")
      (value "LM2576-5.0V")
      (footprint "LM2576-5V")
      (fields (field (name "MF") "Microchip") (field (name "MP") "LM2576-5.0WU"))
      (libsource (lib "greenhouse_SchLib") (part "LM2576-5.0V"))
    )
    (comp (ref "U3")
      (value "ESP32-WROOM-32D")
      (footprint "ESP32-WROOM-32D")
      (fields (field (name "MF") "Espressif Systems"))
      (libsource (lib "greenhouse_SchLib") (part "ESP32-WROOM-32D"))
    )
    (comp (ref "U4")
      (value "AMS1117")
      (footprint "VG 5 - 3.3")
      (description "1A LOW DROPOUT VOLTAGE REGULATOR SOT-223")
      (fields (field (name "MF") "Advanced Monolithic Systems"))
      (libsource (lib "greenhouse_SchLib") (part "VG 5 - 3.3"))
    )
    (comp (ref "U5")
      (value "PC817")
      (footprint "PC817")
      (description "Optocoupler DC-IN 1-CH Transistor DC-OUT 4-Pin DIP SMD T/R")
      (fields (field (name "MF") "Sharp Microelectronics") (field (name "MP") "PC817X2NIP1B"))
      (libsource (lib "greenhouse_SchLib") (part "PC817"))
    )
    (comp (ref "U6")
      (value "PC817")
      (footprint "PC817")
      (description "Optocoupler DC-IN 1-CH Transistor DC-OUT 4-Pin DIP SMD T/R")
      (fields (field (name "MF") "Sharp Microelectronics") (field (name "MP") "PC817X2NIP1B"))
      (libsource (lib "greenhouse_SchLib") (part "PC817"))
    )
    (comp (ref "U7")
      (value "PC817")
      (footprint "PC817")
      (description "Optocoupler DC-IN 1-CH Transistor DC-OUT 4-Pin DIP SMD T/R")
      (fields (field (name "MF") "Sharp Microelectronics") (field (name "MP") "PC817X2NIP1B"))
      (libsource (lib "greenhouse_SchLib") (part "PC817"))
    )
    (comp (ref "U8")
      (value "PC817")
      (footprint "PC817")
      (description "Optocoupler DC-IN 1-CH Transistor DC-OUT 4-Pin DIP SMD T/R")
      (fields (field (name "MF") "Sharp Microelectronics") (field (name "MP") "PC817X2NIP1B"))
      (libsource (lib "greenhouse_SchLib") (part "PC817"))
    )
    (comp (ref "U9")
      (value "PC817")
      (footprint "PC817")
      (description "Optocoupler DC-IN 1-CH Transistor DC-OUT 4-Pin DIP SMD T/R")
      (fields (field (name "MF") "Sharp Microelectronics") (field (name "MP") "PC817X2NIP1B"))
      (libsource (lib "greenhouse_SchLib") (part "PC817"))
    )
    (comp (ref "U10")
      (value "PC817")
      (footprint "PC817")
      (description "Optocoupler DC-IN 1-CH Transistor DC-OUT 4-Pin DIP SMD T/R")
      (fields (field (name "MF") "Sharp Microelectronics") (field (name "MP") "PC817X2NIP1B"))
      (libsource (lib "greenhouse_SchLib") (part "PC817"))
    )
    (comp (ref "U11")
      (value "PC817")
      (footprint "PC817")
      (description "Optocoupler DC-IN 1-CH Transistor DC-OUT 4-Pin DIP SMD T/R")
      (fields (field (name "MF") "Sharp Microelectronics") (field (name "MP") "PC817X2NIP1B"))
      (libsource (lib "greenhouse_SchLib") (part "PC817"))
    )
    (comp (ref "U12")
      (value "PC817")
      (footprint "PC817")
      (description "Optocoupler DC-IN 1-CH Transistor DC-OUT 4-Pin DIP SMD T/R")
      (fields (field (name "MF") "Sharp Microelectronics") (field (name "MP") "PC817X2NIP1B"))
      (libsource (lib "greenhouse_SchLib") (part "PC817"))
    )
    (comp (ref "U13")
      (value "PC817")
      (footprint "PC817")
      (description "Optocoupler DC-IN 1-CH Transistor DC-OUT 4-Pin DIP SMD T/R")
      (fields (field (name "MF") "Sharp Microelectronics") (field (name "MP") "PC817X2NIP1B"))
      (libsource (lib "greenhouse_SchLib") (part "PC817"))
    )
  )
  (nets
    (net (code "1") (name "+3.3") (class "Default")
      (node (ref "C11") (pin "1") (pinfunction "1_1") (pintype "passive"))
      (node (ref "C12") (pin "2") (pinfunction "2_2") (pintype "passive"))
      (node (ref "C6") (pin "1") (pinfunction "1_1") (pintype "passive"))
      (node (ref "C7") (pin "1") (pinfunction "1_1") (pintype "passive"))
      (node (ref "D11") (pin "1") (pinfunction "C_1") (pintype "passive"))
      (node (ref "D12") (pin "1") (pinfunction "C_1") (pintype "passive"))
      (node (ref "D13") (pin "1") (pinfunction "C_1") (pintype "passive"))
      (node (ref "D14") (pin "1") (pinfunction "C_1") (pintype "passive"))
      (node (ref "D6") (pin "1") (pinfunction "C_1") (pintype "passive"))
      (node (ref "D7") (pin "1") (pinfunction "C_1") (pintype "passive"))
      (node (ref "D8") (pin "1") (pinfunction "C_1") (pintype "passive"))
      (node (ref "D9") (pin "1") (pinfunction "C_1") (pintype "passive"))
      (node (ref "J3") (pin "2") (pinfunction "2_2") (pintype "passive"))
      (node (ref "J4") (pin "1") (pinfunction "1_1") (pintype "passive"))
      (node (ref "K1") (pin "COIL1") (pinfunction "COIL1_COIL1") (pintype "passive"))
      (node (ref "K2") (pin "COIL1") (pinfunction "COIL1_COIL1") (pintype "passive"))
      (node (ref "K3") (pin "COIL1") (pinfunction "COIL1_COIL1") (pintype "passive"))
      (node (ref "K4") (pin "COIL1") (pinfunction "COIL1_COIL1") (pintype "passive"))
      (node (ref "K5") (pin "COIL1") (pinfunction "COIL1_COIL1") (pintype "passive"))
      (node (ref "K6") (pin "COIL1") (pinfunction "COIL1_COIL1") (pintype "passive"))
      (node (ref "K7") (pin "COIL1") (pinfunction "COIL1_COIL1") (pintype "passive"))
      (node (ref "K8") (pin "COIL1") (pinfunction "COIL1_COIL1") (pintype "passive"))
      (node (ref "P2") (pin "1") (pinfunction "1_1") (pintype "passive"))
      (node (ref "R1") (pin "2") (pinfunction "2_2") (pintype "passive"))
      (node (ref "R15") (pin "2") (pinfunction "2_2") (pintype "passive"))
      (node (ref "R2") (pin "2") (pinfunction "2_2") (pintype "passive"))
      (node (ref "R3") (pin "2") (pinfunction "2_2") (pintype "passive"))
      (node (ref "R4") (pin "1") (pinfunction "1_1") (pintype "passive"))
      (node (ref "U3") (pin "2") (pinfunction "3V3_2") (pintype "power_in"))
      (node (ref "U4") (pin "2") (pinfunction "VOUT_2") (pintype "output"))
      (node (ref "U4") (pin "4") (pinfunction "VOUT_4") (pintype "passive"))
    )
    (net (code "2") (name "+5") (class "Default")
      (node (ref "C2") (pin "2") (pinfunction "2_2") (pintype "passive"))
      (node (ref "C5") (pin "1") (pinfunction "1_1") (pintype "passive"))
      (node (ref "F2") (pin "1") (pinfunction "1_1") (pintype "passive"))
      (node (ref "J2") (pin "2") (pinfunction "2_2") (pintype "passive"))
      (node (ref "L1") (pin "2") (pinfunction "2_2") (pintype "passive"))
      (node (ref "P1") (pin "1") (pinfunction "1_1") (pintype "passive"))
      (node (ref "P3") (pin "1") (pinfunction "1_1") (pintype "passive"))
      (node (ref "R6") (pin "1") (pinfunction "1_1") (pintype "passive"))
      (node (ref "U10") (pin "4") (pinfunction "CT_4") (pintype "passive"))
      (node (ref "U11") (pin "4") (pinfunction "CT_4") (pintype "passive"))
      (node (ref "U12") (pin "4") (pinfunction "CT_4") (pintype "passive"))
      (node (ref "U13") (pin "4") (pinfunction "CT_4") (pintype "passive"))
      (node (ref "U2") (pin "4") (pinfunction "FEEDBACK_4") (pintype "bidirectional"))
      (node (ref "U5") (pin "4") (pinfunction "CT_4") (pintype "passive"))
      (node (ref "U6") (pin "4") (pinfunction "CT_4") (pintype "passive"))
      (node (ref "U7") (pin "4") (pinfunction "CT_4") (pintype "passive"))
      (node (ref "U8") (pin "4") (pinfunction "CT_4") (pintype "passive"))
      (node (ref "U9") (pin "4") (pinfunction "CT_4") (pintype "passive"))
      (node (ref "f3") (pin "4") (pinfunction "CT_4") (pintype "passive"))
    )
    (net (code "3") (name "+12") (class "Default")
      (node (ref "C4") (pin "1") (pinfunction "1_1") (pintype "passive"))
      (node (ref "F1") (pin "2") (pinfunction "2_2") (pintype "passive"))
      (node (ref "K10") (pin "3") (pinfunction "POS_3") (pintype "power_in"))
      (node (ref "K9") (pin "3") (pinfunction "POS_3") (pintype "power_in"))
      (node (ref "U2") (pin "1") (pinfunction "VIN_1") (pintype "input"))
    )
    (net (code "4") (name "/BOOT") (class "Default")
      (node (ref "R5") (pin "1") (pinfunction "1_1") (pintype "passive"))
      (node (ref "U3") (pin "25") (pinfunction "IO0_25") (pintype "bidirectional"))
    )
    (net (code "5") (name "/Blue") (class "Default")
      (node (ref "D5") (pin "2") (pinfunction "A_2") (pintype "passive"))
      (node (ref "R8") (pin "1") (pinfunction "1_1") (pintype "passive"))
      (node (ref "U3") (pin "37") (pinfunction "IO23_37") (pintype "bidirectional"))
    )
    (net (code "6") (name "/EN") (class "Default")
      (node (ref "C1") (pin "1") (pinfunction "1_1") (pintype "passive"))
      (node (ref "C3") (pin "2") (pinfunction "2_2") (pintype "passive"))
      (node (ref "C8") (pin "2") (pinfunction "2_2") (pintype "passive"))
      (node (ref "R15") (pin "1") (pinfunction "1_1") (pintype "passive"))
      (node (ref "R3") (pin "1") (pinfunction "1_1") (pintype "passive"))
      (node (ref "SW1") (pin "1") (pinfunction "1_1") (pintype "passive"))
      (node (ref "U3") (pin "3") (pinfunction "EN_3") (pintype "input"))
    )
    (net (code "7") (name "/Emit1") (class "Default")
      (node (ref "D15") (pin "1") (pinfunction "K_1") (pintype "passive"))
      (node (ref "R11") (pin "1") (pinfunction "1_1") (pintype "passive"))
    )
    (net (code "8") (name "/Emit2") (class "Default")
      (node (ref "D16") (pin "1") (pinfunction "K_1") (pintype "passive"))
      (node (ref "R12") (pin "1") (pinfunction "1_1") (pintype "passive"))
    )
    (net (code "9") (name "/Emit3") (class "Default")
      (node (ref "D17") (pin "1") (pinfunction "K_1") (pintype "passive"))
      (node (ref "R13") (pin "1") (pinfunction "1_1") (pintype "passive"))
    )
    (net (code "10") (name "/Emit4") (class "Default")
      (node (ref "D18") (pin "1") (pinfunction "K_1") (pintype "passive"))
      (node (ref "R14") (pin "1") (pinfunction "1_1") (pintype "passive"))
    )
    (net (code "11") (name "/Emit5") (class "Default")
      (node (ref "D22") (pin "1") (pinfunction "K_1") (pintype "passive"))
      (node (ref "R16") (pin "1") (pinfunction "1_1") (pintype "passive"))
    )
    (net (code "12") (name "/Emit6") (class "Default")
      (node (ref "D20") (pin "1") (pinfunction "K_1") (pintype "passive"))
      (node (ref "R17") (pin "1") (pinfunction "1_1") (pintype "passive"))
    )
    (net (code "13") (name "/Emit7") (class "Default")
      (node (ref "D23") (pin "1") (pinfunction "K_1") (pintype "passive"))
      (node (ref "R18") (pin "1") (pinfunction "1_1") (pintype "passive"))
    )
    (net (code "14") (name "/Emit8") (class "Default")
      (node (ref "D24") (pin "1") (pinfunction "K_1") (pintype "passive"))
      (node (ref "R19") (pin "1") (pinfunction "1_1") (pintype "passive"))
    )
    (net (code "15") (name "/Emit9") (class "Default")
      (node (ref "D21") (pin "1") (pinfunction "K_1") (pintype "passive"))
      (node (ref "R36") (pin "1") (pinfunction "1_1") (pintype "passive"))
    )
    (net (code "16") (name "/Emit10") (class "Default")
      (node (ref "D19") (pin "1") (pinfunction "K_1") (pintype "passive"))
      (node (ref "R37") (pin "1") (pinfunction "1_1") (pintype "passive"))
    )
    (net (code "17") (name "/PIN4") (class "Default")
      (node (ref "P1") (pin "2") (pinfunction "2_2") (pintype "passive"))
      (node (ref "R6") (pin "2") (pinfunction "2_2") (pintype "passive"))
      (node (ref "U3") (pin "26") (pinfunction "IO4_26") (pintype "bidirectional"))
    )
    (net (code "18") (name "/RX") (class "Default")
      (node (ref "J4") (pin "2") (pinfunction "2_2") (pintype "passive"))
      (node (ref "P3") (pin "2") (pinfunction "2_2") (pintype "passive"))
      (node (ref "U3") (pin "34") (pinfunction "RXD0_34") (pintype "bidirectional"))
    )
    (net (code "19") (name "/Red") (class "Default")
      (node (ref "D4") (pin "2") (pinfunction "A_2") (pintype "passive"))
      (node (ref "R7") (pin "1") (pinfunction "1_1") (pintype "passive"))
      (node (ref "U3") (pin "31") (pinfunction "IO19_31") (pintype "bidirectional"))
    )
    (net (code "20") (name "/Relay1") (class "Default")
      (node (ref "R20") (pin "2") (pinfunction "2_2") (pintype "passive"))
      (node (ref "U3") (pin "16") (pinfunction "IO13_16") (pintype "bidirectional"))
    )
    (net (code "21") (name "/Relay2") (class "Default")
      (node (ref "R21") (pin "2") (pinfunction "2_2") (pintype "passive"))
      (node (ref "U3") (pin "13") (pinfunction "IO14_13") (pintype "bidirectional"))
    )
    (net (code "22") (name "/Relay3") (class "Default")
      (node (ref "R24") (pin "2") (pinfunction "2_2") (pintype "passive"))
      (node (ref "U3") (pin "27") (pinfunction "IO16_27") (pintype "bidirectional"))
    )
    (net (code "23") (name "/Relay4") (class "Default")
      (node (ref "R25") (pin "2") (pinfunction "2_2") (pintype "passive"))
      (node (ref "U3") (pin "28") (pinfunction "IO17_28") (pintype "bidirectional"))
    )
    (net (code "24") (name "/Relay5") (class "Default")
      (node (ref "R33") (pin "2") (pinfunction "2_2") (pintype "passive"))
      (node (ref "U3") (pin "30") (pinfunction "IO18_30") (pintype "bidirectional"))
    )
    (net (code "25") (name "/Relay6") (class "Default")
      (node (ref "R30") (pin "2") (pinfunction "2_2") (pintype "passive"))
      (node (ref "U3") (pin "10") (pinfunction "IO25_10") (pintype "bidirectional"))
    )
    (net (code "26") (name "/Relay7") (class "Default")
      (node (ref "R31") (pin "2") (pinfunction "2_2") (pintype "passive"))
      (node (ref "U3") (pin "11") (pinfunction "IO26_11") (pintype "bidirectional"))
    )
    (net (code "27") (name "/Relay8") (class "Default")
      (node (ref "R32") (pin "2") (pinfunction "2_2") (pintype "passive"))
      (node (ref "U3") (pin "12") (pinfunction "IO27_12") (pintype "bidirectional"))
    )
    (net (code "28") (name "/RelayIN1_1") (class "Default")
      (node (ref "D6") (pin "2") (pinfunction "A_2") (pintype "passive"))
      (node (ref "K1") (pin "COIL2") (pinfunction "COIL2_COIL2") (pintype "passive"))
      (node (ref "Q2") (pin "2") (pinfunction "C_2") (pintype "passive"))
      (node (ref "Q2") (pin "4") (pinfunction "C_4") (pintype "passive"))
    )
    (net (code "29") (name "/RelayIN2_1") (class "Default")
      (node (ref "D7") (pin "2") (pinfunction "A_2") (pintype "passive"))
      (node (ref "K2") (pin "COIL2") (pinfunction "COIL2_COIL2") (pintype "passive"))
      (node (ref "Q3") (pin "2") (pinfunction "C_2") (pintype "passive"))
      (node (ref "Q3") (pin "4") (pinfunction "C_4") (pintype "passive"))
    )
    (net (code "30") (name "/RelayIN3_1") (class "Default")
      (node (ref "D8") (pin "2") (pinfunction "A_2") (pintype "passive"))
      (node (ref "K3") (pin "COIL2") (pinfunction "COIL2_COIL2") (pintype "passive"))
      (node (ref "Q4") (pin "2") (pinfunction "C_2") (pintype "passive"))
      (node (ref "Q4") (pin "4") (pinfunction "C_4") (pintype "passive"))
    )
    (net (code "31") (name "/RelayIN4_1") (class "Default")
      (node (ref "D9") (pin "2") (pinfunction "A_2") (pintype "passive"))
      (node (ref "K4") (pin "COIL2") (pinfunction "COIL2_COIL2") (pintype "passive"))
      (node (ref "Q5") (pin "2") (pinfunction "C_2") (pintype "passive"))
      (node (ref "Q5") (pin "4") (pinfunction "C_4") (pintype "passive"))
    )
    (net (code "32") (name "/RelayIN5_1") (class "Default")
      (node (ref "D11") (pin "2") (pinfunction "A_2") (pintype "passive"))
      (node (ref "K5") (pin "COIL2") (pinfunction "COIL2_COIL2") (pintype "passive"))
      (node (ref "Q6") (pin "2") (pinfunction "C_2") (pintype "passive"))
      (node (ref "Q6") (pin "4") (pinfunction "C_4") (pintype "passive"))
    )
    (net (code "33") (name "/RelayIN6_1") (class "Default")
      (node (ref "D12") (pin "2") (pinfunction "A_2") (pintype "passive"))
      (node (ref "K6") (pin "COIL2") (pinfunction "COIL2_COIL2") (pintype "passive"))
      (node (ref "Q7") (pin "2") (pinfunction "C_2") (pintype "passive"))
      (node (ref "Q7") (pin "4") (pinfunction "C_4") (pintype "passive"))
    )
    (net (code "34") (name "/RelayIN7_1") (class "Default")
      (node (ref "D13") (pin "2") (pinfunction "A_2") (pintype "passive"))
      (node (ref "K7") (pin "COIL2") (pinfunction "COIL2_COIL2") (pintype "passive"))
      (node (ref "Q8") (pin "2") (pinfunction "C_2") (pintype "passive"))
      (node (ref "Q8") (pin "4") (pinfunction "C_4") (pintype "passive"))
    )
    (net (code "35") (name "/RelayIN8_1") (class "Default")
      (node (ref "D14") (pin "2") (pinfunction "A_2") (pintype "passive"))
      (node (ref "K8") (pin "COIL2") (pinfunction "COIL2_COIL2") (pintype "passive"))
      (node (ref "Q9") (pin "2") (pinfunction "C_2") (pintype "passive"))
      (node (ref "Q9") (pin "4") (pinfunction "C_4") (pintype "passive"))
    )
    (net (code "36") (name "/SCL") (class "Default")
      (node (ref "P2") (pin "3") (pinfunction "3_3") (pintype "passive"))
      (node (ref "R2") (pin "1") (pinfunction "1_1") (pintype "passive"))
      (node (ref "U3") (pin "36") (pinfunction "IO22_36") (pintype "bidirectional"))
    )
    (net (code "37") (name "/SDA") (class "Default")
      (node (ref "P2") (pin "2") (pinfunction "2_2") (pintype "passive"))
      (node (ref "R1") (pin "1") (pinfunction "1_1") (pintype "passive"))
      (node (ref "U3") (pin "33") (pinfunction "IO21_33") (pintype "bidirectional"))
    )
    (net (code "38") (name "/SSR1") (class "Default")
      (node (ref "R28") (pin "2") (pinfunction "2_2") (pintype "passive"))
      (node (ref "U3") (pin "8") (pinfunction "IO32_8") (pintype "bidirectional"))
    )
    (net (code "39") (name "/SSR2") (class "Default")
      (node (ref "R29") (pin "2") (pinfunction "2_2") (pintype "passive"))
      (node (ref "U3") (pin "9") (pinfunction "IO33_9") (pintype "bidirectional"))
    )
    (net (code "40") (name "/TX") (class "Default")
      (node (ref "J4") (pin "3") (pinfunction "3_3") (pintype "passive"))
      (node (ref "P3") (pin "3") (pinfunction "3_3") (pintype "passive"))
      (node (ref "U3") (pin "35") (pinfunction "TXD0_35") (pintype "bidirectional"))
    )
    (net (code "41") (name "GND") (class "Default")
      (node (ref "C1") (pin "2") (pinfunction "2_2") (pintype "passive"))
      (node (ref "C10") (pin "1") (pinfunction "1_1") (pintype "passive"))
      (node (ref "C11") (pin "2") (pinfunction "2_2") (pintype "passive"))
      (node (ref "C12") (pin "1") (pinfunction "1_1") (pintype "passive"))
      (node (ref "C2") (pin "1") (pinfunction "1_1") (pintype "passive"))
      (node (ref "C3") (pin "1") (pinfunction "1_1") (pintype "passive"))
      (node (ref "C4") (pin "2") (pinfunction "2_2") (pintype "passive"))
      (node (ref "C5") (pin "2") (pinfunction "2_2") (pintype "passive"))
      (node (ref "C6") (pin "2") (pinfunction "2_2") (pintype "passive"))
      (node (ref "C7") (pin "2") (pinfunction "2_2") (pintype "passive"))
      (node (ref "C8") (pin "1") (pinfunction "1_1") (pintype "passive"))
      (node (ref "C9") (pin "2") (pinfunction "2_2") (pintype "passive"))
      (node (ref "D1") (pin "2") (pinfunction "K_2") (pintype "passive"))
      (node (ref "D10") (pin "A") (pinfunction "A_A") (pintype "passive"))
      (node (ref "D3") (pin "2") (pinfunction "K_2") (pintype "passive"))
      (node (ref "J1") (pin "1") (pinfunction "1_1") (pintype "passive"))
      (node (ref "J2") (pin "1") (pinfunction "1_1") (pintype "passive"))
      (node (ref "J3") (pin "1") (pinfunction "1_1") (pintype "passive"))
      (node (ref "J4") (pin "4") (pinfunction "4_4") (pintype "passive"))
      (node (ref "P1") (pin "4") (pinfunction "4_4") (pintype "passive"))
      (node (ref "P2") (pin "4") (pinfunction "4_4") (pintype "passive"))
      (node (ref "P3") (pin "4") (pinfunction "4_4") (pintype "passive"))
      (node (ref "Q1") (pin "3") (pinfunction "E_3") (pintype "passive"))
      (node (ref "Q10") (pin "3") (pinfunction "E_3") (pintype "passive"))
      (node (ref "Q11") (pin "3") (pinfunction "E_3") (pintype "passive"))
      (node (ref "Q2") (pin "3") (pinfunction "E_3") (pintype "passive"))
      (node (ref "Q3") (pin "3") (pinfunction "E_3") (pintype "passive"))
      (node (ref "Q4") (pin "3") (pinfunction "E_3") (pintype "passive"))
      (node (ref "Q5") (pin "3") (pinfunction "E_3") (pintype "passive"))
      (node (ref "Q6") (pin "3") (pinfunction "E_3") (pintype "passive"))
      (node (ref "Q7") (pin "3") (pinfunction "E_3") (pintype "passive"))
      (node (ref "Q8") (pin "3") (pinfunction "E_3") (pintype "passive"))
      (node (ref "Q9") (pin "3") (pinfunction "E_3") (pintype "passive"))
      (node (ref "R10") (pin "1") (pinfunction "1_1") (pintype "passive"))
      (node (ref "SW1") (pin "2") (pinfunction "2_2") (pintype "passive"))
      (node (ref "SW2") (pin "2") (pinfunction "2_2") (pintype "passive"))
      (node (ref "U10") (pin "2") (pinfunction "C_2") (pintype "passive"))
      (node (ref "U11") (pin "2") (pinfunction "C_2") (pintype "passive"))
      (node (ref "U12") (pin "2") (pinfunction "C_2") (pintype "passive"))
      (node (ref "U13") (pin "2") (pinfunction "C_2") (pintype "passive"))
      (node (ref "U2") (pin "3") (pinfunction "GROUND_3") (pintype "power_in"))
      (node (ref "U2") (pin "5") (pinfunction "~{ON}/OFF_5") (pintype "input"))
      (node (ref "U2") (pin "6") (pinfunction "GROUND_6") (pintype "power_in"))
      (node (ref "U3") (pin "1") (pinfunction "GND_1") (pintype "power_in"))
      (node (ref "U3") (pin "15") (pinfunction "GND_15") (pintype "power_in"))
      (node (ref "U3") (pin "38") (pinfunction "GND_38") (pintype "power_in"))
      (node (ref "U3") (pin "39_1") (pinfunction "GND_39_1") (pintype "power_in"))
      (node (ref "U3") (pin "39_10") (pinfunction "GND_39_10") (pintype "power_in"))
      (node (ref "U3") (pin "39_11") (pinfunction "GND_39_11") (pintype "power_in"))
      (node (ref "U3") (pin "39_12") (pinfunction "GND_39_12") (pintype "power_in"))
      (node (ref "U3") (pin "39_13") (pinfunction "GND_39_13") (pintype "power_in"))
      (node (ref "U3") (pin "39_14") (pinfunction "GND_39_14") (pintype "power_in"))
      (node (ref "U3") (pin "39_15") (pinfunction "GND_39_15") (pintype "power_in"))
      (node (ref "U3") (pin "39_16") (pinfunction "GND_39_16") (pintype "power_in"))
      (node (ref "U3") (pin "39_17") (pinfunction "GND_39_17") (pintype "power_in"))
      (node (ref "U3") (pin "39_18") (pinfunction "GND_39_18") (pintype "power_in"))
      (node (ref "U3") (pin "39_19") (pinfunction "GND_39_19") (pintype "power_in"))
      (node (ref "U3") (pin "39_2") (pinfunction "GND_39_2") (pintype "power_in"))
      (node (ref "U3") (pin "39_20") (pinfunction "GND_39_20") (pintype "power_in"))
      (node (ref "U3") (pin "39_21") (pinfunction "GND_39_21") (pintype "power_in"))
      (node (ref "U3") (pin "39_3") (pinfunction "GND_39_3") (pintype "power_in"))
      (node (ref "U3") (pin "39_4") (pinfunction "GND_39_4") (pintype "power_in"))
      (node (ref "U3") (pin "39_5") (pinfunction "GND_39_5") (pintype "power_in"))
      (node (ref "U3") (pin "39_6") (pinfunction "GND_39_6") (pintype "power_in"))
      (node (ref "U3") (pin "39_7") (pinfunction "GND_39_7") (pintype "power_in"))
      (node (ref "U3") (pin "39_8") (pinfunction "GND_39_8") (pintype "power_in"))
      (node (ref "U3") (pin "39_9") (pinfunction "GND_39_9") (pintype "power_in"))
      (node (ref "U4") (pin "1") (pinfunction "ADJ/GND_1") (pintype "power_in"))
      (node (ref "U5") (pin "2") (pinfunction "C_2") (pintype "passive"))
      (node (ref "U6") (pin "2") (pinfunction "C_2") (pintype "passive"))
      (node (ref "U7") (pin "2") (pinfunction "C_2") (pintype "passive"))
      (node (ref "U8") (pin "2") (pinfunction "C_2") (pintype "passive"))
      (node (ref "U9") (pin "2") (pinfunction "C_2") (pintype "passive"))
      (node (ref "f3") (pin "2") (pinfunction "C_2") (pintype "passive"))
    )
    (net (code "42") (name "Net-(D1-A)") (class "Default")
      (node (ref "D1") (pin "1") (pinfunction "A_1") (pintype "passive"))
      (node (ref "R7") (pin "2") (pinfunction "2_2") (pintype "passive"))
    )
    (net (code "43") (name "Net-(D2-A)") (class "Default")
      (node (ref "D2") (pin "1") (pinfunction "A_1") (pintype "passive"))
      (node (ref "R4") (pin "2") (pinfunction "2_2") (pintype "passive"))
    )
    (net (code "44") (name "Net-(D2-K)") (class "Default")
      (node (ref "D2") (pin "2") (pinfunction "K_2") (pintype "passive"))
      (node (ref "Q1") (pin "2") (pinfunction "C_2") (pintype "passive"))
      (node (ref "Q1") (pin "4") (pinfunction "C_4") (pintype "passive"))
    )
    (net (code "45") (name "Net-(D3-A)") (class "Default")
      (node (ref "D3") (pin "1") (pinfunction "A_1") (pintype "passive"))
      (node (ref "R8") (pin "2") (pinfunction "2_2") (pintype "passive"))
    )
    (net (code "46") (name "Net-(D4-C)") (class "Default")
      (node (ref "D4") (pin "1") (pinfunction "C_1") (pintype "passive"))
      (node (ref "D5") (pin "1") (pinfunction "C_1") (pintype "passive"))
      (node (ref "R9") (pin "1") (pinfunction "1_1") (pintype "passive"))
    )
    (net (code "47") (name "Net-(D15-A)") (class "Default")
      (node (ref "D15") (pin "2") (pinfunction "A_2") (pintype "passive"))
      (node (ref "R22") (pin "1") (pinfunction "1_1") (pintype "passive"))
    )
    (net (code "48") (name "Net-(D16-A)") (class "Default")
      (node (ref "D16") (pin "2") (pinfunction "A_2") (pintype "passive"))
      (node (ref "R23") (pin "1") (pinfunction "1_1") (pintype "passive"))
    )
    (net (code "49") (name "Net-(D17-A)") (class "Default")
      (node (ref "D17") (pin "2") (pinfunction "A_2") (pintype "passive"))
      (node (ref "R26") (pin "1") (pinfunction "1_1") (pintype "passive"))
    )
    (net (code "50") (name "Net-(D18-A)") (class "Default")
      (node (ref "D18") (pin "2") (pinfunction "A_2") (pintype "passive"))
      (node (ref "R27") (pin "1") (pinfunction "1_1") (pintype "passive"))
    )
    (net (code "51") (name "Net-(D19-A)") (class "Default")
      (node (ref "D19") (pin "2") (pinfunction "A_2") (pintype "passive"))
      (node (ref "R35") (pin "1") (pinfunction "1_1") (pintype "passive"))
    )
    (net (code "52") (name "Net-(D20-A)") (class "Default")
      (node (ref "D20") (pin "2") (pinfunction "A_2") (pintype "passive"))
      (node (ref "R38") (pin "1") (pinfunction "1_1") (pintype "passive"))
    )
    (net (code "53") (name "Net-(D21-A)") (class "Default")
      (node (ref "D21") (pin "2") (pinfunction "A_2") (pintype "passive"))
      (node (ref "R34") (pin "1") (pinfunction "1_1") (pintype "passive"))
    )
    (net (code "54") (name "Net-(D22-A)") (class "Default")
      (node (ref "D22") (pin "2") (pinfunction "A_2") (pintype "passive"))
      (node (ref "R41") (pin "1") (pinfunction "1_1") (pintype "passive"))
    )
    (net (code "55") (name "Net-(D23-A)") (class "Default")
      (node (ref "D23") (pin "2") (pinfunction "A_2") (pintype "passive"))
      (node (ref "R39") (pin "1") (pinfunction "1_1") (pintype "passive"))
    )
    (net (code "56") (name "Net-(D24-A)") (class "Default")
      (node (ref "D24") (pin "2") (pinfunction "A_2") (pintype "passive"))
      (node (ref "R40") (pin "1") (pinfunction "1_1") (pintype "passive"))
    )
    (net (code "57") (name "Net-(F1-Pad1)") (class "Default")
      (node (ref "F1") (pin "1") (pinfunction "1_1") (pintype "passive"))
      (node (ref "J1") (pin "2") (pinfunction "2_2") (pintype "passive"))
    )
    (net (code "58") (name "Net-(J5-Pad1)") (class "Default")
      (node (ref "J5") (pin "1") (pinfunction "1_1") (pintype "passive"))
      (node (ref "K1") (pin "COM") (pinfunction "COM_COM") (pintype "passive"))
    )
    (net (code "59") (name "Net-(J5-Pad2)") (class "Default")
      (node (ref "J5") (pin "2") (pinfunction "2_2") (pintype "passive"))
      (node (ref "K1") (pin "NO") (pinfunction "NO_NO") (pintype "passive"))
    )
    (net (code "60") (name "Net-(J6-Pad1)") (class "Default")
      (node (ref "J6") (pin "1") (pinfunction "1_1") (pintype "passive"))
      (node (ref "K2") (pin "COM") (pinfunction "COM_COM") (pintype "passive"))
    )
    (net (code "61") (name "Net-(J6-Pad2)") (class "Default")
      (node (ref "J6") (pin "2") (pinfunction "2_2") (pintype "passive"))
      (node (ref "K2") (pin "NO") (pinfunction "NO_NO") (pintype "passive"))
    )
    (net (code "62") (name "Net-(J7-Pad1)") (class "Default")
      (node (ref "J7") (pin "1") (pinfunction "1_1") (pintype "passive"))
      (node (ref "K3") (pin "COM") (pinfunction "COM_COM") (pintype "passive"))
    )
    (net (code "63") (name "Net-(J7-Pad2)") (class "Default")
      (node (ref "J7") (pin "2") (pinfunction "2_2") (pintype "passive"))
      (node (ref "K3") (pin "NO") (pinfunction "NO_NO") (pintype "passive"))
    )
    (net (code "64") (name "Net-(J8-Pad1)") (class "Default")
      (node (ref "J8") (pin "1") (pinfunction "1_1") (pintype "passive"))
      (node (ref "K4") (pin "COM") (pinfunction "COM_COM") (pintype "passive"))
    )
    (net (code "65") (name "Net-(J8-Pad2)") (class "Default")
      (node (ref "J8") (pin "2") (pinfunction "2_2") (pintype "passive"))
      (node (ref "K4") (pin "NO") (pinfunction "NO_NO") (pintype "passive"))
    )
    (net (code "66") (name "Net-(J9-Pad1)") (class "Default")
      (node (ref "J9") (pin "1") (pinfunction "1_1") (pintype "passive"))
      (node (ref "K5") (pin "COM") (pinfunction "COM_COM") (pintype "passive"))
    )
    (net (code "67") (name "Net-(J9-Pad2)") (class "Default")
      (node (ref "J9") (pin "2") (pinfunction "2_2") (pintype "passive"))
      (node (ref "K5") (pin "NO") (pinfunction "NO_NO") (pintype "passive"))
    )
    (net (code "68") (name "Net-(J10-Pad1)") (class "Default")
      (node (ref "J10") (pin "1") (pinfunction "1_1") (pintype "passive"))
      (node (ref "K6") (pin "COM") (pinfunction "COM_COM") (pintype "passive"))
    )
    (net (code "69") (name "Net-(J10-Pad2)") (class "Default")
      (node (ref "J10") (pin "2") (pinfunction "2_2") (pintype "passive"))
      (node (ref "K6") (pin "NO") (pinfunction "NO_NO") (pintype "passive"))
    )
    (net (code "70") (name "Net-(J11-Pad1)") (class "Default")
      (node (ref "J11") (pin "1") (pinfunction "1_1") (pintype "passive"))
      (node (ref "K7") (pin "COM") (pinfunction "COM_COM") (pintype "passive"))
    )
    (net (code "71") (name "Net-(J11-Pad2)") (class "Default")
      (node (ref "J11") (pin "2") (pinfunction "2_2") (pintype "passive"))
      (node (ref "K7") (pin "NO") (pinfunction "NO_NO") (pintype "passive"))
    )
    (net (code "72") (name "Net-(J12-Pad1)") (class "Default")
      (node (ref "J12") (pin "1") (pinfunction "1_1") (pintype "passive"))
      (node (ref "K8") (pin "COM") (pinfunction "COM_COM") (pintype "passive"))
    )
    (net (code "73") (name "Net-(J12-Pad2)") (class "Default")
      (node (ref "J12") (pin "2") (pinfunction "2_2") (pintype "passive"))
      (node (ref "K8") (pin "NO") (pinfunction "NO_NO") (pintype "passive"))
    )
    (net (code "74") (name "Net-(J13-1)") (class "Default")
      (node (ref "J13") (pin "2") (pinfunction "1_2") (pintype "passive"))
      (node (ref "K9") (pin "2") (pinfunction "L2_2") (pintype "power_in"))
    )
    (net (code "75") (name "Net-(J13-2)") (class "Default")
      (node (ref "J13") (pin "1") (pinfunction "2_1") (pintype "passive"))
      (node (ref "K9") (pin "1") (pinfunction "L1_1") (pintype "power_in"))
    )
    (net (code "76") (name "Net-(J14-1)") (class "Default")
      (node (ref "J14") (pin "2") (pinfunction "1_2") (pintype "passive"))
      (node (ref "K10") (pin "2") (pinfunction "L2_2") (pintype "power_in"))
    )
    (net (code "77") (name "Net-(J14-2)") (class "Default")
      (node (ref "J14") (pin "1") (pinfunction "2_1") (pintype "passive"))
      (node (ref "K10") (pin "1") (pinfunction "L1_1") (pintype "power_in"))
    )
    (net (code "78") (name "Net-(K9-NEG)") (class "Default")
      (node (ref "K9") (pin "4") (pinfunction "NEG_4") (pintype "power_in"))
      (node (ref "Q10") (pin "2") (pinfunction "C_2") (pintype "passive"))
      (node (ref "Q10") (pin "4") (pinfunction "C_4") (pintype "passive"))
    )
    (net (code "79") (name "Net-(K10-NEG)") (class "Default")
      (node (ref "K10") (pin "4") (pinfunction "NEG_4") (pintype "power_in"))
      (node (ref "Q11") (pin "2") (pinfunction "C_2") (pintype "passive"))
      (node (ref "Q11") (pin "4") (pinfunction "C_4") (pintype "passive"))
    )
    (net (code "80") (name "Net-(Q1-B)") (class "Default")
      (node (ref "Q1") (pin "1") (pinfunction "B_1") (pintype "passive"))
      (node (ref "R10") (pin "2") (pinfunction "2_2") (pintype "passive"))
      (node (ref "R9") (pin "2") (pinfunction "2_2") (pintype "passive"))
    )
    (net (code "81") (name "Net-(Q2-B)") (class "Default")
      (node (ref "Q2") (pin "1") (pinfunction "B_1") (pintype "passive"))
      (node (ref "R11") (pin "2") (pinfunction "2_2") (pintype "passive"))
    )
    (net (code "82") (name "Net-(Q3-B)") (class "Default")
      (node (ref "Q3") (pin "1") (pinfunction "B_1") (pintype "passive"))
      (node (ref "R12") (pin "2") (pinfunction "2_2") (pintype "passive"))
    )
    (net (code "83") (name "Net-(Q4-B)") (class "Default")
      (node (ref "Q4") (pin "1") (pinfunction "B_1") (pintype "passive"))
      (node (ref "R13") (pin "2") (pinfunction "2_2") (pintype "passive"))
    )
    (net (code "84") (name "Net-(Q5-B)") (class "Default")
      (node (ref "Q5") (pin "1") (pinfunction "B_1") (pintype "passive"))
      (node (ref "R14") (pin "2") (pinfunction "2_2") (pintype "passive"))
    )
    (net (code "85") (name "Net-(Q6-B)") (class "Default")
      (node (ref "Q6") (pin "1") (pinfunction "B_1") (pintype "passive"))
      (node (ref "R16") (pin "2") (pinfunction "2_2") (pintype "passive"))
    )
    (net (code "86") (name "Net-(Q7-B)") (class "Default")
      (node (ref "Q7") (pin "1") (pinfunction "B_1") (pintype "passive"))
      (node (ref "R17") (pin "2") (pinfunction "2_2") (pintype "passive"))
    )
    (net (code "87") (name "Net-(Q8-B)") (class "Default")
      (node (ref "Q8") (pin "1") (pinfunction "B_1") (pintype "passive"))
      (node (ref "R18") (pin "2") (pinfunction "2_2") (pintype "passive"))
    )
    (net (code "88") (name "Net-(Q9-B)") (class "Default")
      (node (ref "Q9") (pin "1") (pinfunction "B_1") (pintype "passive"))
      (node (ref "R19") (pin "2") (pinfunction "2_2") (pintype "passive"))
    )
    (net (code "89") (name "Net-(Q10-B)") (class "Default")
      (node (ref "Q10") (pin "1") (pinfunction "B_1") (pintype "passive"))
      (node (ref "R36") (pin "2") (pinfunction "2_2") (pintype "passive"))
    )
    (net (code "90") (name "Net-(Q11-B)") (class "Default")
      (node (ref "Q11") (pin "1") (pinfunction "B_1") (pintype "passive"))
      (node (ref "R37") (pin "2") (pinfunction "2_2") (pintype "passive"))
    )
    (net (code "91") (name "Net-(R5-Pad2)") (class "Default")
      (node (ref "R5") (pin "2") (pinfunction "2_2") (pintype "passive"))
      (node (ref "SW2") (pin "1") (pinfunction "1_1") (pintype "passive"))
    )
    (net (code "92") (name "Net-(U2-OUTPUT)") (class "Default")
      (node (ref "D10") (pin "C") (pinfunction "C_C") (pintype "passive"))
      (node (ref "L1") (pin "1") (pinfunction "1_1") (pintype "passive"))
      (node (ref "U2") (pin "2") (pinfunction "OUTPUT_2") (pintype "output"))
    )
    (net (code "93") (name "Net-(U4-VIN)") (class "Default")
      (node (ref "C10") (pin "2") (pinfunction "2_2") (pintype "passive"))
      (node (ref "C9") (pin "1") (pinfunction "1_1") (pintype "passive"))
      (node (ref "F2") (pin "2") (pinfunction "2_2") (pintype "passive"))
      (node (ref "U4") (pin "3") (pinfunction "VIN_3") (pintype "input"))
    )
    (net (code "94") (name "Net-(U5-A)") (class "Default")
      (node (ref "R20") (pin "1") (pinfunction "1_1") (pintype "passive"))
      (node (ref "U5") (pin "1") (pinfunction "A_1") (pintype "passive"))
    )
    (net (code "95") (name "Net-(U5-ET)") (class "Default")
      (node (ref "R22") (pin "2") (pinfunction "2_2") (pintype "passive"))
      (node (ref "U5") (pin "3") (pinfunction "ET_3") (pintype "passive"))
    )
    (net (code "96") (name "Net-(U6-A)") (class "Default")
      (node (ref "R24") (pin "1") (pinfunction "1_1") (pintype "passive"))
      (node (ref "U6") (pin "1") (pinfunction "A_1") (pintype "passive"))
    )
    (net (code "97") (name "Net-(U6-ET)") (class "Default")
      (node (ref "R26") (pin "2") (pinfunction "2_2") (pintype "passive"))
      (node (ref "U6") (pin "3") (pinfunction "ET_3") (pintype "passive"))
    )
    (net (code "98") (name "Net-(U7-A)") (class "Default")
      (node (ref "R25") (pin "1") (pinfunction "1_1") (pintype "passive"))
      (node (ref "U7") (pin "1") (pinfunction "A_1") (pintype "passive"))
    )
    (net (code "99") (name "Net-(U7-ET)") (class "Default")
      (node (ref "R27") (pin "2") (pinfunction "2_2") (pintype "passive"))
      (node (ref "U7") (pin "3") (pinfunction "ET_3") (pintype "passive"))
    )
    (net (code "100") (name "Net-(U8-A)") (class "Default")
      (node (ref "R28") (pin "1") (pinfunction "1_1") (pintype "passive"))
      (node (ref "U8") (pin "1") (pinfunction "A_1") (pintype "passive"))
    )
    (net (code "101") (name "Net-(U8-ET)") (class "Default")
      (node (ref "R34") (pin "2") (pinfunction "2_2") (pintype "passive"))
      (node (ref "U8") (pin "3") (pinfunction "ET_3") (pintype "passive"))
    )
    (net (code "102") (name "Net-(U9-A)") (class "Default")
      (node (ref "R29") (pin "1") (pinfunction "1_1") (pintype "passive"))
      (node (ref "U9") (pin "1") (pinfunction "A_1") (pintype "passive"))
    )
    (net (code "103") (name "Net-(U9-ET)") (class "Default")
      (node (ref "R35") (pin "2") (pinfunction "2_2") (pintype "passive"))
      (node (ref "U9") (pin "3") (pinfunction "ET_3") (pintype "passive"))
    )
    (net (code "104") (name "Net-(U10-A)") (class "Default")
      (node (ref "R30") (pin "1") (pinfunction "1_1") (pintype "passive"))
      (node (ref "U10") (pin "1") (pinfunction "A_1") (pintype "passive"))
    )
    (net (code "105") (name "Net-(U10-ET)") (class "Default")
      (node (ref "R38") (pin "2") (pinfunction "2_2") (pintype "passive"))
      (node (ref "U10") (pin "3") (pinfunction "ET_3") (pintype "passive"))
    )
    (net (code "106") (name "Net-(U11-A)") (class "Default")
      (node (ref "R31") (pin "1") (pinfunction "1_1") (pintype "passive"))
      (node (ref "U11") (pin "1") (pinfunction "A_1") (pintype "passive"))
    )
    (net (code "107") (name "Net-(U11-ET)") (class "Default")
      (node (ref "R39") (pin "2") (pinfunction "2_2") (pintype "passive"))
      (node (ref "U11") (pin "3") (pinfunction "ET_3") (pintype "passive"))
    )
    (net (code "108") (name "Net-(U12-A)") (class "Default")
      (node (ref "R32") (pin "1") (pinfunction "1_1") (pintype "passive"))
      (node (ref "U12") (pin "1") (pinfunction "A_1") (pintype "passive"))
    )
    (net (code "109") (name "Net-(U12-ET)") (class "Default")
      (node (ref "R40") (pin "2") (pinfunction "2_2") (pintype "passive"))
      (node (ref "U12") (pin "3") (pinfunction "ET_3") (pintype "passive"))
    )
    (net (code "110") (name "Net-(U13-A)") (class "Default")
      (node (ref "R33") (pin "1") (pinfunction "1_1") (pintype "passive"))
      (node (ref "U13") (pin "1") (pinfunction "A_1") (pintype "passive"))
    )
    (net (code "111") (name "Net-(U13-ET)") (class "Default")
      (node (ref "R41") (pin "2") (pinfunction "2_2") (pintype "passive"))
      (node (ref "U13") (pin "3") (pinfunction "ET_3") (pintype "passive"))
    )
    (net (code "112") (name "Net-(f3-A)") (class "Default")
      (node (ref "R21") (pin "1") (pinfunction "1_1") (pintype "passive"))
      (node (ref "f3") (pin "1") (pinfunction "A_1") (pintype "passive"))
    )
    (net (code "113") (name "Net-(f3-ET)") (class "Default")
      (node (ref "R23") (pin "2") (pinfunction "2_2") (pintype "passive"))
      (node (ref "f3") (pin "3") (pinfunction "ET_3") (pintype "passive"))
    )
    (net (code "114") (name "unconnected-(K1-PadNC)") (class "Default")
      (node (ref "K1") (pin "NC") (pinfunction "NC_NC") (pintype "passive"))
    )
    (net (code "115") (name "unconnected-(K2-PadNC)") (class "Default")
      (node (ref "K2") (pin "NC") (pinfunction "NC_NC") (pintype "passive"))
    )
    (net (code "116") (name "unconnected-(K3-PadNC)") (class "Default")
      (node (ref "K3") (pin "NC") (pinfunction "NC_NC") (pintype "passive"))
    )
    (net (code "117") (name "unconnected-(K4-PadNC)") (class "Default")
      (node (ref "K4") (pin "NC") (pinfunction "NC_NC") (pintype "passive+no_connect"))
    )
    (net (code "118") (name "unconnected-(K5-PadNC)") (class "Default")
      (node (ref "K5") (pin "NC") (pinfunction "NC_NC") (pintype "passive"))
    )
    (net (code "119") (name "unconnected-(K6-PadNC)") (class "Default")
      (node (ref "K6") (pin "NC") (pinfunction "NC_NC") (pintype "passive"))
    )
    (net (code "120") (name "unconnected-(K7-PadNC)") (class "Default")
      (node (ref "K7") (pin "NC") (pinfunction "NC_NC") (pintype "passive"))
    )
    (net (code "121") (name "unconnected-(K8-PadNC)") (class "Default")
      (node (ref "K8") (pin "NC") (pinfunction "NC_NC") (pintype "passive+no_connect"))
    )
    (net (code "122") (name "unconnected-(P1-Pad3)") (class "Default")
      (node (ref "P1") (pin "3") (pinfunction "3_3") (pintype "passive"))
    )
    (net (code "123") (name "unconnected-(U3-IO2-Pad24)") (class "Default")
      (node (ref "U3") (pin "24") (pinfunction "IO2_24") (pintype "bidirectional"))
    )
    (net (code "124") (name "unconnected-(U3-IO5-Pad29)") (class "Default")
      (node (ref "U3") (pin "29") (pinfunction "IO5_29") (pintype "bidirectional"))
    )
    (net (code "125") (name "unconnected-(U3-IO12-Pad14)") (class "Default")
      (node (ref "U3") (pin "14") (pinfunction "IO12_14") (pintype "bidirectional"))
    )
    (net (code "126") (name "unconnected-(U3-IO15-Pad23)") (class "Default")
      (node (ref "U3") (pin "23") (pinfunction "IO15_23") (pintype "bidirectional"))
    )
    (net (code "127") (name "unconnected-(U3-IO34-Pad6)") (class "Default")
      (node (ref "U3") (pin "6") (pinfunction "IO34_6") (pintype "input+no_connect"))
    )
    (net (code "128") (name "unconnected-(U3-IO35-Pad7)") (class "Default")
      (node (ref "U3") (pin "7") (pinfunction "IO35_7") (pintype "input+no_connect"))
    )
    (net (code "129") (name "unconnected-(U3-SCK{slash}CLK-Pad20)") (class "Default")
      (node (ref "U3") (pin "20") (pinfunction "SCK/CLK_20") (pintype "bidirectional+no_connect"))
    )
    (net (code "130") (name "unconnected-(U3-SCS{slash}CMD-Pad19)") (class "Default")
      (node (ref "U3") (pin "19") (pinfunction "SCS/CMD_19") (pintype "bidirectional+no_connect"))
    )
    (net (code "131") (name "unconnected-(U3-SDI{slash}SD1-Pad22)") (class "Default")
      (node (ref "U3") (pin "22") (pinfunction "SDI/SD1_22") (pintype "bidirectional+no_connect"))
    )
    (net (code "132") (name "unconnected-(U3-SDO{slash}SD0-Pad21)") (class "Default")
      (node (ref "U3") (pin "21") (pinfunction "SDO/SD0_21") (pintype "bidirectional+no_connect"))
    )
    (net (code "133") (name "unconnected-(U3-SENSOR_VN-Pad5)") (class "Default")
      (node (ref "U3") (pin "5") (pinfunction "SENSOR_VN_5") (pintype "input+no_connect"))
    )
    (net (code "134") (name "unconnected-(U3-SENSOR_VP-Pad4)") (class "Default")
      (node (ref "U3") (pin "4") (pinfunction "SENSOR_VP_4") (pintype "input+no_connect"))
    )
    (net (code "135") (name "unconnected-(U3-SHD{slash}SD2-Pad17)") (class "Default")
      (node (ref "U3") (pin "17") (pinfunction "SHD/SD2_17") (pintype "bidirectional+no_connect"))
    )
    (net (code "136") (name "unconnected-(U3-SWP{slash}SD3-Pad18)") (class "Default")
      (node (ref "U3") (pin "18") (pinfunction "SWP/SD3_18") (pintype "bidirectional+no_connect"))
    )
  )
)
